# Stepper_motor_board.net
KiCad netlist of a schematic drawn in EAGLE
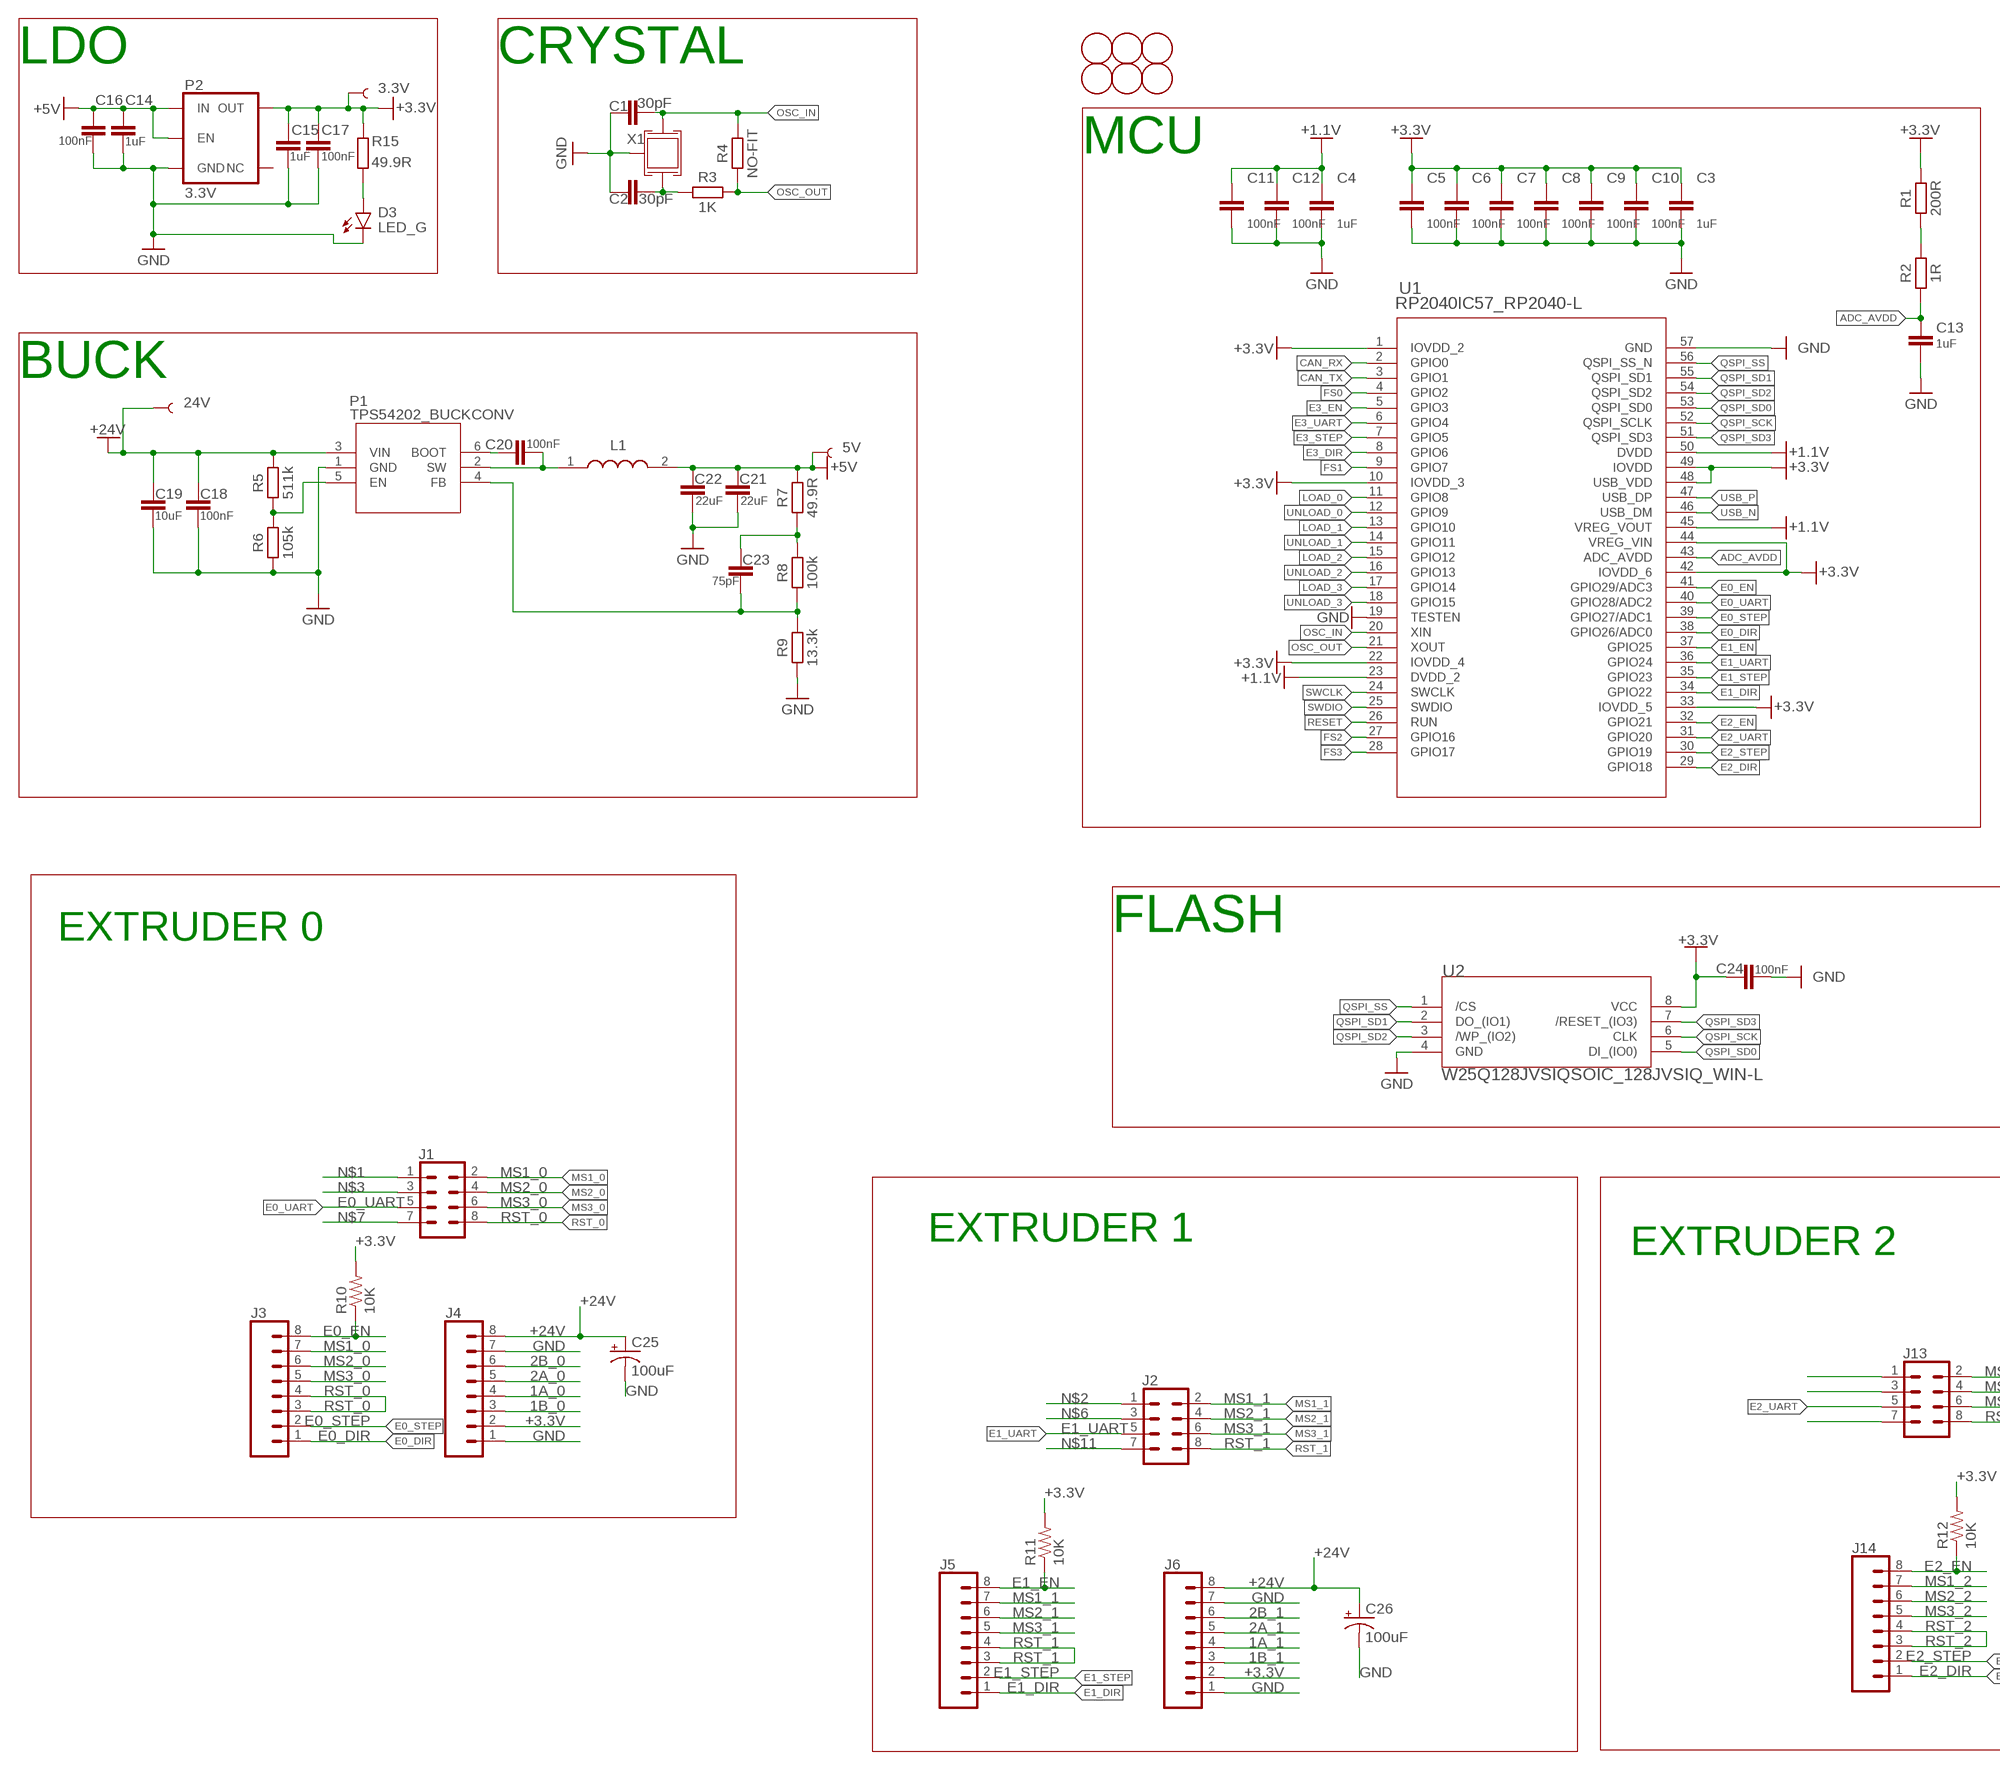
[diagram p0: schematic, sheet 1, part 1 of 2]
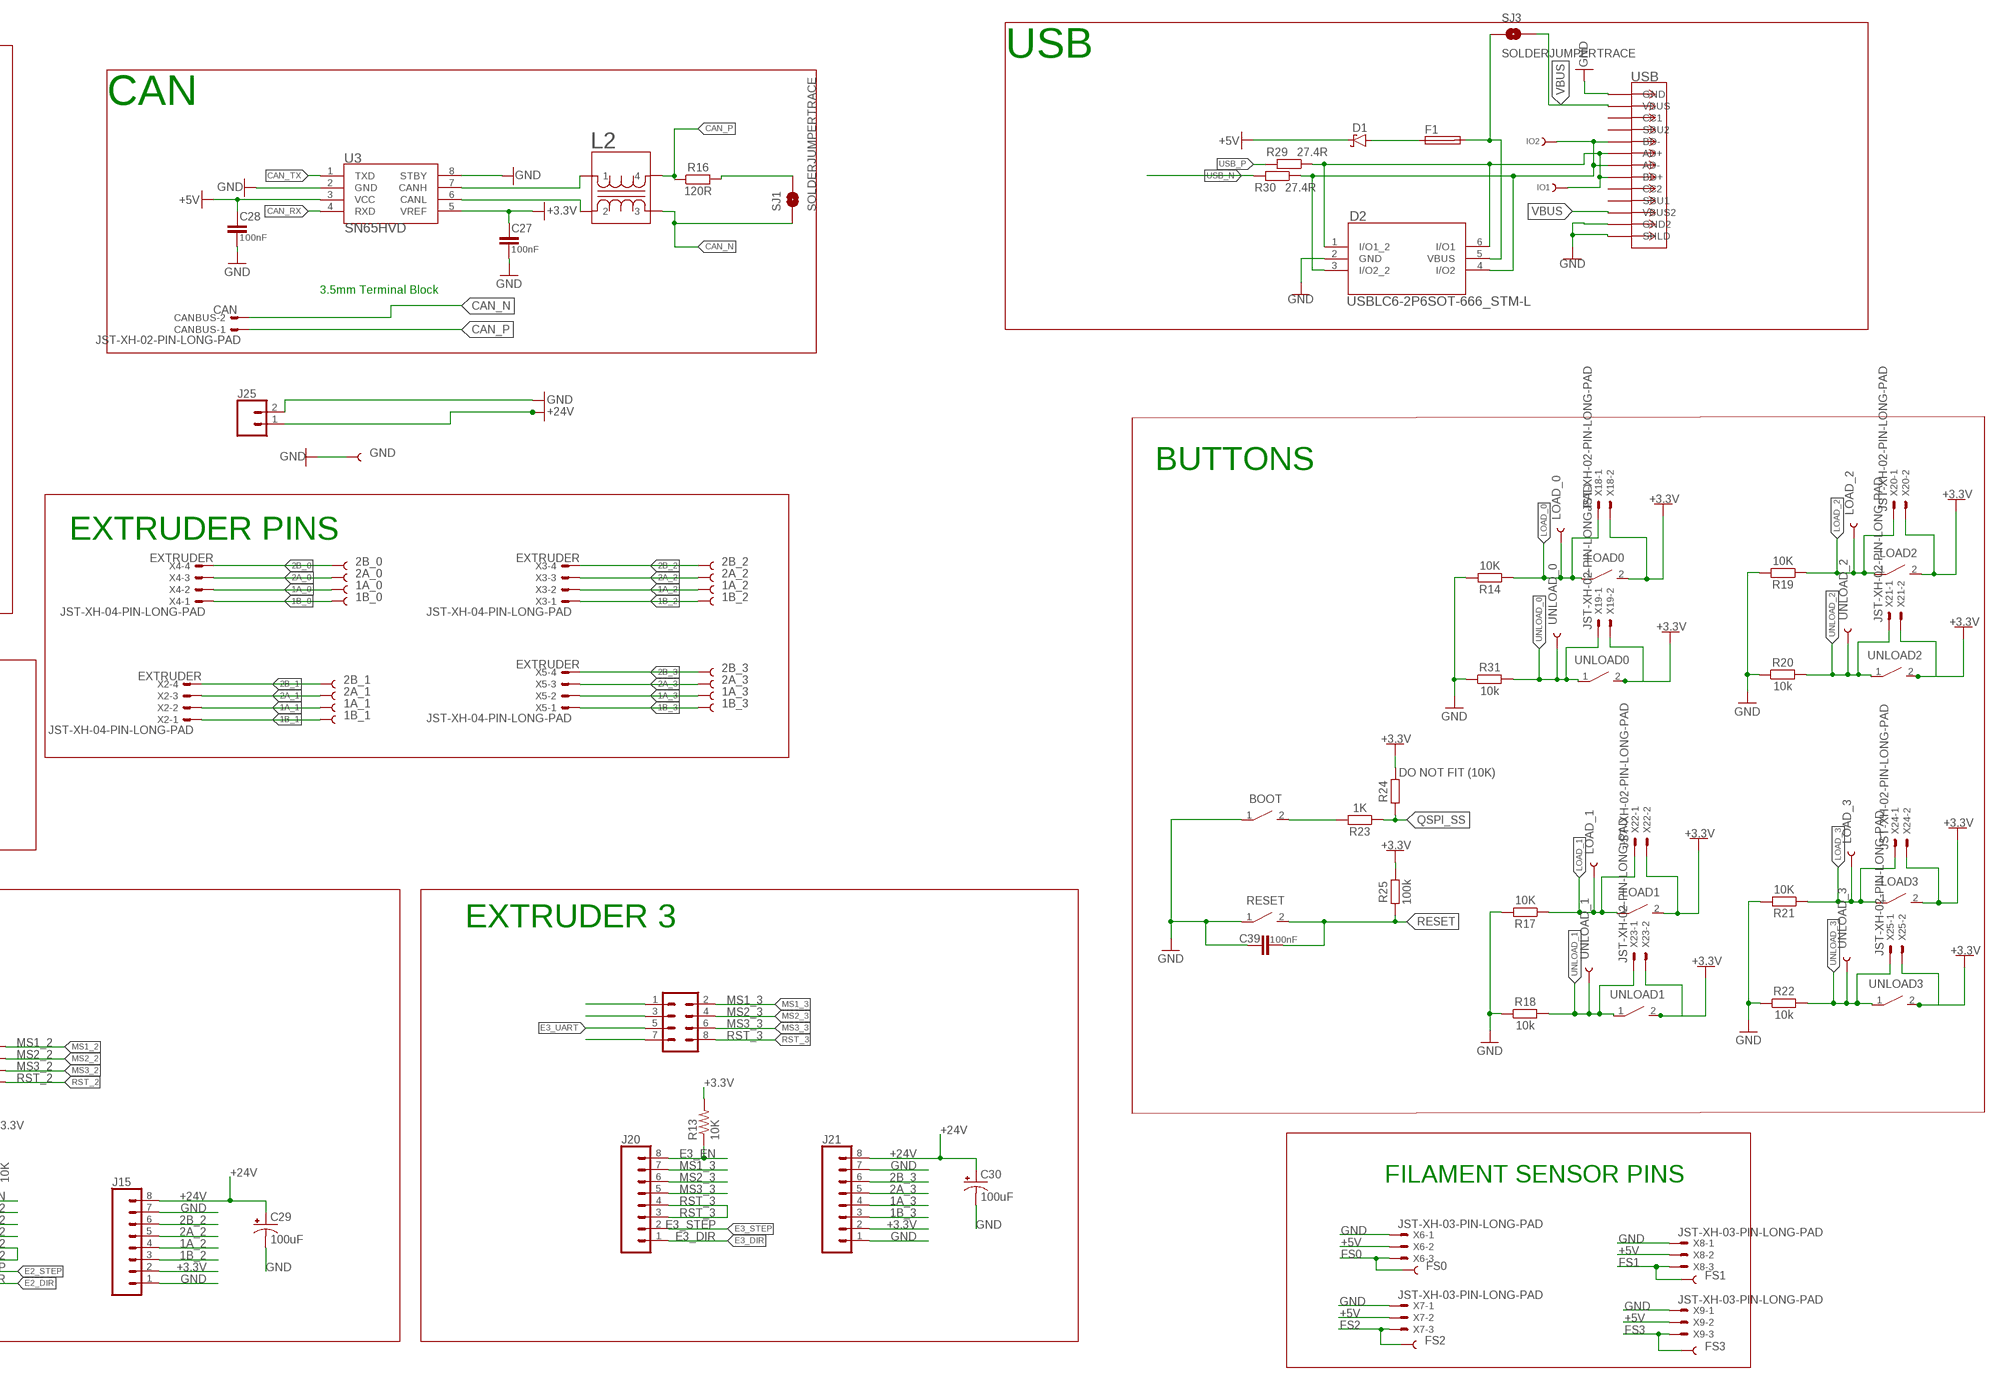
[diagram p1: schematic, sheet 1, part 2 of 2]

(export (version "E")
  (design (tool "Eeschema 10.0.6"))
  (components
    (comp (ref "1A_0")
      (value "TEST-POINT3X4")
      (footprint "eagle-import:PAD.03X.04")
      (libsource (lib "eagle-import") (part "TEST-POINT3X4"))
    )
    (comp (ref "1A_1")
      (value "TEST-POINT3X4")
      (footprint "eagle-import:PAD.03X.04")
      (libsource (lib "eagle-import") (part "TEST-POINT3X4"))
    )
    (comp (ref "1A_2")
      (value "TEST-POINT3X4")
      (footprint "eagle-import:PAD.03X.04")
      (libsource (lib "eagle-import") (part "TEST-POINT3X4"))
    )
    (comp (ref "1A_3")
      (value "TEST-POINT3X4")
      (footprint "eagle-import:PAD.03X.04")
      (libsource (lib "eagle-import") (part "TEST-POINT3X4"))
    )
    (comp (ref "1B_0")
      (value "TEST-POINT3X4")
      (footprint "eagle-import:PAD.03X.04")
      (libsource (lib "eagle-import") (part "TEST-POINT3X4"))
    )
    (comp (ref "1B_1")
      (value "TEST-POINT3X4")
      (footprint "eagle-import:PAD.03X.04")
      (libsource (lib "eagle-import") (part "TEST-POINT3X4"))
    )
    (comp (ref "1B_2")
      (value "TEST-POINT3X4")
      (footprint "eagle-import:PAD.03X.04")
      (libsource (lib "eagle-import") (part "TEST-POINT3X4"))
    )
    (comp (ref "1B_3")
      (value "TEST-POINT3X4")
      (footprint "eagle-import:PAD.03X.04")
      (libsource (lib "eagle-import") (part "TEST-POINT3X4"))
    )
    (comp (ref "2A_0")
      (value "TEST-POINT3X4")
      (footprint "eagle-import:PAD.03X.04")
      (libsource (lib "eagle-import") (part "TEST-POINT3X4"))
    )
    (comp (ref "2A_1")
      (value "TEST-POINT3X4")
      (footprint "eagle-import:PAD.03X.04")
      (libsource (lib "eagle-import") (part "TEST-POINT3X4"))
    )
    (comp (ref "2A_2")
      (value "TEST-POINT3X4")
      (footprint "eagle-import:PAD.03X.04")
      (libsource (lib "eagle-import") (part "TEST-POINT3X4"))
    )
    (comp (ref "2A_3")
      (value "TEST-POINT3X4")
      (footprint "eagle-import:PAD.03X.04")
      (libsource (lib "eagle-import") (part "TEST-POINT3X4"))
    )
    (comp (ref "2B_0")
      (value "TEST-POINT3X4")
      (footprint "eagle-import:PAD.03X.04")
      (libsource (lib "eagle-import") (part "TEST-POINT3X4"))
    )
    (comp (ref "2B_1")
      (value "TEST-POINT3X4")
      (footprint "eagle-import:PAD.03X.04")
      (libsource (lib "eagle-import") (part "TEST-POINT3X4"))
    )
    (comp (ref "2B_2")
      (value "TEST-POINT3X4")
      (footprint "eagle-import:PAD.03X.04")
      (libsource (lib "eagle-import") (part "TEST-POINT3X4"))
    )
    (comp (ref "2B_3")
      (value "TEST-POINT3X4")
      (footprint "eagle-import:PAD.03X.04")
      (libsource (lib "eagle-import") (part "TEST-POINT3X4"))
    )
    (comp (ref "3.3V")
      (value "TEST-POINT3X4")
      (footprint "eagle-import:PAD.03X.04")
      (libsource (lib "eagle-import") (part "TEST-POINT3X4"))
    )
    (comp (ref "5V")
      (value "TEST-POINT3X4")
      (footprint "eagle-import:PAD.03X.04")
      (libsource (lib "eagle-import") (part "TEST-POINT3X4"))
    )
    (comp (ref "24V")
      (value "TEST-POINT3X4")
      (footprint "eagle-import:PAD.03X.04")
      (libsource (lib "eagle-import") (part "TEST-POINT3X4"))
    )
    (comp (ref "BOOT")
      (value "B3U-1000P(M)-B")
      (footprint "eagle-import:B3U-1000P(M)-B")
      (fields (field (name "MANUFACTURER") "OMRON"))
      (libsource (lib "eagle-import") (part "B3U-X0001000P(M)-BB3U-1000P(M)-B"))
    )
    (comp (ref "C1")
      (value "30pF")
      (footprint "eagle-import:CAPC1005X60")
      (libsource (lib "eagle-import") (part "CCHIP-0402(1005-METRIC)_"))
    )
    (comp (ref "C2")
      (value "30pF")
      (footprint "eagle-import:CAPC1005X60")
      (libsource (lib "eagle-import") (part "CCHIP-0402(1005-METRIC)_"))
    )
    (comp (ref "C3")
      (value "1uF")
      (footprint "eagle-import:CAPC1005X60")
      (libsource (lib "eagle-import") (part "CCHIP-0402(1005-METRIC)_"))
    )
    (comp (ref "C4")
      (value "1uF")
      (footprint "eagle-import:CAPC1005X60")
      (libsource (lib "eagle-import") (part "CCHIP-0402(1005-METRIC)_"))
    )
    (comp (ref "C5")
      (value "100nF")
      (footprint "eagle-import:CAPC1005X60")
      (libsource (lib "eagle-import") (part "CCHIP-0402(1005-METRIC)_"))
    )
    (comp (ref "C6")
      (value "100nF")
      (footprint "eagle-import:CAPC1005X60")
      (libsource (lib "eagle-import") (part "CCHIP-0402(1005-METRIC)_"))
    )
    (comp (ref "C7")
      (value "100nF")
      (footprint "eagle-import:CAPC1005X60")
      (libsource (lib "eagle-import") (part "CCHIP-0402(1005-METRIC)_"))
    )
    (comp (ref "C8")
      (value "100nF")
      (footprint "eagle-import:CAPC1005X60")
      (libsource (lib "eagle-import") (part "CCHIP-0402(1005-METRIC)_"))
    )
    (comp (ref "C9")
      (value "100nF")
      (footprint "eagle-import:CAPC1005X60")
      (libsource (lib "eagle-import") (part "CCHIP-0402(1005-METRIC)_"))
    )
    (comp (ref "C10")
      (value "100nF")
      (footprint "eagle-import:CAPC1005X60")
      (libsource (lib "eagle-import") (part "CCHIP-0402(1005-METRIC)_"))
    )
    (comp (ref "C11")
      (value "100nF")
      (footprint "eagle-import:CAPC1005X60")
      (libsource (lib "eagle-import") (part "CCHIP-0402(1005-METRIC)_"))
    )
    (comp (ref "C12")
      (value "100nF")
      (footprint "eagle-import:CAPC1005X60")
      (libsource (lib "eagle-import") (part "CCHIP-0402(1005-METRIC)_"))
    )
    (comp (ref "C13")
      (value "1uF")
      (footprint "eagle-import:CAPC1005X60")
      (libsource (lib "eagle-import") (part "CCHIP-0402(1005-METRIC)_"))
    )
    (comp (ref "C14")
      (value "1uF")
      (footprint "eagle-import:CAPC1005X60")
      (libsource (lib "eagle-import") (part "CCHIP-0402(1005-METRIC)_"))
    )
    (comp (ref "C15")
      (value "1uF")
      (footprint "eagle-import:CAPC1005X60")
      (libsource (lib "eagle-import") (part "CCHIP-0402(1005-METRIC)_"))
    )
    (comp (ref "C16")
      (value "100nF")
      (footprint "eagle-import:CAPC1005X60")
      (libsource (lib "eagle-import") (part "CCHIP-0402(1005-METRIC)_"))
    )
    (comp (ref "C17")
      (value "100nF")
      (footprint "eagle-import:CAPC1005X60")
      (libsource (lib "eagle-import") (part "CCHIP-0402(1005-METRIC)_"))
    )
    (comp (ref "C18")
      (value "100nF")
      (footprint "eagle-import:CAPC1005X60")
      (libsource (lib "eagle-import") (part "CCHIP-0402(1005-METRIC)_"))
    )
    (comp (ref "C19")
      (value "10uF")
      (footprint "eagle-import:CAPC1608X85")
      (libsource (lib "eagle-import") (part "CCHIP-0603(1608-METRIC)_"))
    )
    (comp (ref "C20")
      (value "100nF")
      (footprint "eagle-import:CAPC1005X60")
      (libsource (lib "eagle-import") (part "CCHIP-0402(1005-METRIC)_"))
    )
    (comp (ref "C21")
      (value "22uF")
      (footprint "eagle-import:CAPC2012X110")
      (libsource (lib "eagle-import") (part "CCHIP-0805(2012-METRIC)_"))
    )
    (comp (ref "C22")
      (value "22uF")
      (footprint "eagle-import:CAPC2012X110")
      (libsource (lib "eagle-import") (part "CCHIP-0805(2012-METRIC)_"))
    )
    (comp (ref "C23")
      (value "75pF")
      (footprint "eagle-import:CAPC1005X60")
      (libsource (lib "eagle-import") (part "CCHIP-0402(1005-METRIC)_"))
    )
    (comp (ref "C24")
      (value "100nF")
      (footprint "eagle-import:CAPC1005X60")
      (libsource (lib "eagle-import") (part "CCHIP-0402(1005-METRIC)_"))
    )
    (comp (ref "C25")
      (value "100uF")
      (footprint "eagle-import:PANASONIC_D")
      (libsource (lib "eagle-import") (part "100UF-POLAR-25V-20%(ELEC)"))
    )
    (comp (ref "C26")
      (value "100uF")
      (footprint "eagle-import:PANASONIC_D")
      (libsource (lib "eagle-import") (part "100UF-POLAR-25V-20%(ELEC)"))
    )
    (comp (ref "C27")
      (value "100nF")
      (footprint "eagle-import:CAPC1005X60")
      (libsource (lib "eagle-import") (part "CCHIP-0402(1005-METRIC)_"))
    )
    (comp (ref "C28")
      (value "100nF")
      (footprint "eagle-import:CAPC1005X60")
      (libsource (lib "eagle-import") (part "CCHIP-0402(1005-METRIC)_"))
    )
    (comp (ref "C29")
      (value "100uF")
      (footprint "eagle-import:PANASONIC_D")
      (libsource (lib "eagle-import") (part "100UF-POLAR-25V-20%(ELEC)"))
    )
    (comp (ref "C30")
      (value "100uF")
      (footprint "eagle-import:PANASONIC_D")
      (libsource (lib "eagle-import") (part "100UF-POLAR-25V-20%(ELEC)"))
    )
    (comp (ref "C39")
      (value "100nF")
      (footprint "eagle-import:CAPC1005X60")
      (libsource (lib "eagle-import") (part "CCHIP-0402(1005-METRIC)_"))
    )
    (comp (ref "CANBUS")
      (value "JST-XH-02-PIN-LONG-PAD")
      (footprint "eagle-import:JST-XH-02-PACKAGE-LONG-PAD")
      (libsource (lib "eagle-import") (part "JST-XH-02-PIN-LONG-PAD"))
    )
    (comp (ref "D1")
      (value "MBR0520LT1G")
      (footprint "eagle-import:SODFL3718X115")
      (fields (field (name "MANUFACTURER") "ON Semiconductor"))
      (libsource (lib "eagle-import") (part "SCHOTTKY_DO-219MBR0520LT1G"))
    )
    (comp (ref "D2")
      (value "USBLC6-2P6SOT-666_STM-L")
      (footprint "eagle-import:SOT-666_STM-L")
      (fields
        (field (name "MANUFACTURER_PART_NUMBER") "USBLC6-2P6")
        (field (name "COPYRIGHT") "Copyright (C) 2023 Ultra Librarian. All rights reserved.")
      )
      (libsource (lib "eagle-import") (part "USBLC6-2P6SOT-666_STM-L"))
    )
    (comp (ref "D3")
      (value "LED_G")
      (footprint "eagle-import:LEDC1608X35N_FLAT-G")
      (libsource (lib "eagle-import") (part "CHIP-FLAT-G_0603-0.35MM"))
    )
    (comp (ref "F1")
      (value "FUSE_CHIP-0603(1608-METRIC)")
      (footprint "eagle-import:FUSC1608X60N")
      (libsource (lib "eagle-import") (part "FUSECHIP-0603(1608-METRIC)_"))
    )
    (comp (ref "FD1")
      (value "FIDUCIAL")
      (footprint "eagle-import:FIDUCIAL_1MM")
      (libsource (lib "eagle-import") (part "FIDUCIAL"))
    )
    (comp (ref "FD2")
      (value "FIDUCIAL")
      (footprint "eagle-import:FIDUCIAL_1MM")
      (libsource (lib "eagle-import") (part "FIDUCIAL"))
    )
    (comp (ref "FD3")
      (value "FIDUCIAL")
      (footprint "eagle-import:FIDUCIAL_1MM")
      (libsource (lib "eagle-import") (part "FIDUCIAL"))
    )
    (comp (ref "FD4")
      (value "FIDUCIAL")
      (footprint "eagle-import:FIDUCIAL_1MM")
      (libsource (lib "eagle-import") (part "FIDUCIAL"))
    )
    (comp (ref "FD5")
      (value "FIDUCIAL")
      (footprint "eagle-import:FIDUCIAL_1MM")
      (libsource (lib "eagle-import") (part "FIDUCIAL"))
    )
    (comp (ref "FD6")
      (value "FIDUCIAL")
      (footprint "eagle-import:FIDUCIAL_1MM")
      (libsource (lib "eagle-import") (part "FIDUCIAL"))
    )
    (comp (ref "FS0")
      (value "TEST-POINT3X4")
      (footprint "eagle-import:PAD.03X.04")
      (libsource (lib "eagle-import") (part "TEST-POINT3X4"))
    )
    (comp (ref "FS1")
      (value "TEST-POINT3X4")
      (footprint "eagle-import:PAD.03X.04")
      (libsource (lib "eagle-import") (part "TEST-POINT3X4"))
    )
    (comp (ref "FS2")
      (value "TEST-POINT3X4")
      (footprint "eagle-import:PAD.03X.04")
      (libsource (lib "eagle-import") (part "TEST-POINT3X4"))
    )
    (comp (ref "FS3")
      (value "TEST-POINT3X4")
      (footprint "eagle-import:PAD.03X.04")
      (libsource (lib "eagle-import") (part "TEST-POINT3X4"))
    )
    (comp (ref "GND")
      (value "TEST-POINT3X4")
      (footprint "eagle-import:PAD.03X.04")
      (libsource (lib "eagle-import") (part "TEST-POINT3X4"))
    )
    (comp (ref "IO1")
      (value "TEST-POINT3")
      (footprint "eagle-import:PAD.03X.03")
      (libsource (lib "eagle-import") (part "TEST-POINT3"))
    )
    (comp (ref "IO2")
      (value "TEST-POINT3")
      (footprint "eagle-import:PAD.03X.03")
      (libsource (lib "eagle-import") (part "TEST-POINT3"))
    )
    (comp (ref "J1")
      (value "CONN_04X2")
      (footprint "eagle-import:2X4")
      (libsource (lib "eagle-import") (part "CONN_04X2"))
    )
    (comp (ref "J2")
      (value "CONN_04X2")
      (footprint "eagle-import:2X4")
      (libsource (lib "eagle-import") (part "CONN_04X2"))
    )
    (comp (ref "J3")
      (value "CONN_08\"")
      (footprint "eagle-import:1X08")
      (libsource (lib "eagle-import") (part "CONN_08{dblquote}"))
    )
    (comp (ref "J4")
      (value "CONN_08\"")
      (footprint "eagle-import:1X08")
      (libsource (lib "eagle-import") (part "CONN_08{dblquote}"))
    )
    (comp (ref "J5")
      (value "CONN_08\"")
      (footprint "eagle-import:1X08")
      (libsource (lib "eagle-import") (part "CONN_08{dblquote}"))
    )
    (comp (ref "J6")
      (value "CONN_08\"")
      (footprint "eagle-import:1X08")
      (libsource (lib "eagle-import") (part "CONN_08{dblquote}"))
    )
    (comp (ref "J13")
      (value "CONN_04X2")
      (footprint "eagle-import:2X4")
      (libsource (lib "eagle-import") (part "CONN_04X2"))
    )
    (comp (ref "J14")
      (value "CONN_08\"")
      (footprint "eagle-import:1X08")
      (libsource (lib "eagle-import") (part "CONN_08{dblquote}"))
    )
    (comp (ref "J15")
      (value "CONN_08\"")
      (footprint "eagle-import:1X08")
      (libsource (lib "eagle-import") (part "CONN_08{dblquote}"))
    )
    (comp (ref "J19")
      (value "CONN_04X2")
      (footprint "eagle-import:2X4")
      (libsource (lib "eagle-import") (part "CONN_04X2"))
    )
    (comp (ref "J20")
      (value "CONN_08\"")
      (footprint "eagle-import:1X08")
      (libsource (lib "eagle-import") (part "CONN_08{dblquote}"))
    )
    (comp (ref "J21")
      (value "CONN_08\"")
      (footprint "eagle-import:1X08")
      (libsource (lib "eagle-import") (part "CONN_08{dblquote}"))
    )
    (comp (ref "J25")
      (value "CONN_023.5MM")
      (footprint "eagle-import:SCREWTERMINAL-3.5MM-2")
      (libsource (lib "eagle-import") (part "CONN_023.5MM"))
    )
    (comp (ref "L1")
      (value "ASPI-0630HI-100M-T157X7X4")
      (footprint "eagle-import:SMDRI74-680MT")
      (libsource (lib "eagle-import") (part "ASPI-0630HI-100M-T157X7X4"))
    )
    (comp (ref "L2")
      (value "ACM2012")
      (footprint "eagle-import:ACM2012_TDK")
      (fields
        (field (name "MANUFACTURER_PART_NUMBER") "ACM2012-201-2P-T002")
        (field (name "COPYRIGHT") "Copyright (C) 2023 Ultra Librarian. All rights reserved.")
      )
      (libsource (lib "eagle-import") (part "ACM2012-201-2P-T002ACM2012_TDK"))
    )
    (comp (ref "LOAD0")
      (value "B3U-1000P(M)-B")
      (footprint "eagle-import:B3U-1000P(M)-B")
      (fields (field (name "MANUFACTURER") "OMRON"))
      (libsource (lib "eagle-import") (part "B3U-X0001000P(M)-BB3U-1000P(M)-B"))
    )
    (comp (ref "LOAD1")
      (value "B3U-1000P(M)-B")
      (footprint "eagle-import:B3U-1000P(M)-B")
      (fields (field (name "MANUFACTURER") "OMRON"))
      (libsource (lib "eagle-import") (part "B3U-X0001000P(M)-BB3U-1000P(M)-B"))
    )
    (comp (ref "LOAD2")
      (value "B3U-1000P(M)-B")
      (footprint "eagle-import:B3U-1000P(M)-B")
      (fields (field (name "MANUFACTURER") "OMRON"))
      (libsource (lib "eagle-import") (part "B3U-X0001000P(M)-BB3U-1000P(M)-B"))
    )
    (comp (ref "LOAD3")
      (value "B3U-1000P(M)-B")
      (footprint "eagle-import:B3U-1000P(M)-B")
      (fields (field (name "MANUFACTURER") "OMRON"))
      (libsource (lib "eagle-import") (part "B3U-X0001000P(M)-BB3U-1000P(M)-B"))
    )
    (comp (ref "LOAD_0")
      (value "TEST-POINT3X4")
      (footprint "eagle-import:PAD.03X.04")
      (libsource (lib "eagle-import") (part "TEST-POINT3X4"))
    )
    (comp (ref "LOAD_1")
      (value "TEST-POINT3X4")
      (footprint "eagle-import:PAD.03X.04")
      (libsource (lib "eagle-import") (part "TEST-POINT3X4"))
    )
    (comp (ref "LOAD_2")
      (value "TEST-POINT3X4")
      (footprint "eagle-import:PAD.03X.04")
      (libsource (lib "eagle-import") (part "TEST-POINT3X4"))
    )
    (comp (ref "LOAD_3")
      (value "TEST-POINT3X4")
      (footprint "eagle-import:PAD.03X.04")
      (libsource (lib "eagle-import") (part "TEST-POINT3X4"))
    )
    (comp (ref "P1")
      (value "TPS54202_BUCKCONV")
      (footprint "eagle-import:SOT-23-6")
      (libsource (lib "eagle-import") (part "TPS54202_BUCKCONV"))
    )
    (comp (ref "P2")
      (value "3.3V")
      (footprint "eagle-import:SOT23-5")
      (libsource (lib "eagle-import") (part "V_REG_AP2112K-3.3V"))
    )
    (comp (ref "R1")
      (value "200R")
      (footprint "eagle-import:RESC1005X40")
      (libsource (lib "eagle-import") (part "RCHIP-0402(1005-METRIC)_"))
    )
    (comp (ref "R2")
      (value "1R")
      (footprint "eagle-import:RESC1005X40")
      (libsource (lib "eagle-import") (part "RCHIP-0402(1005-METRIC)_"))
    )
    (comp (ref "R3")
      (value "1K")
      (footprint "eagle-import:RESC1005X40")
      (libsource (lib "eagle-import") (part "RCHIP-0402(1005-METRIC)_"))
    )
    (comp (ref "R4")
      (value "NO-FIT")
      (footprint "eagle-import:RESC1005X40")
      (libsource (lib "eagle-import") (part "RCHIP-0402(1005-METRIC)_"))
    )
    (comp (ref "R5")
      (value "511k")
      (footprint "eagle-import:RESC1005X40")
      (libsource (lib "eagle-import") (part "RCHIP-0402(1005-METRIC)_"))
    )
    (comp (ref "R6")
      (value "105k")
      (footprint "eagle-import:RESC1005X40")
      (libsource (lib "eagle-import") (part "RCHIP-0402(1005-METRIC)_"))
    )
    (comp (ref "R7")
      (value "49.9R")
      (footprint "eagle-import:RESC1005X40")
      (libsource (lib "eagle-import") (part "RCHIP-0402(1005-METRIC)_"))
    )
    (comp (ref "R8")
      (value "100k")
      (footprint "eagle-import:RESC1005X40")
      (libsource (lib "eagle-import") (part "RCHIP-0402(1005-METRIC)_"))
    )
    (comp (ref "R9")
      (value "13.3k")
      (footprint "eagle-import:RESC1005X40")
      (libsource (lib "eagle-import") (part "RCHIP-0402(1005-METRIC)_"))
    )
    (comp (ref "R10")
      (value "10K")
      (footprint "eagle-import:0603-RES")
      (libsource (lib "eagle-import") (part "10KOHM1/10W1%(0603)0603"))
    )
    (comp (ref "R11")
      (value "10K")
      (footprint "eagle-import:0603-RES")
      (libsource (lib "eagle-import") (part "10KOHM1/10W1%(0603)0603"))
    )
    (comp (ref "R12")
      (value "10K")
      (footprint "eagle-import:0603-RES")
      (libsource (lib "eagle-import") (part "10KOHM1/10W1%(0603)0603"))
    )
    (comp (ref "R13")
      (value "10K")
      (footprint "eagle-import:0603-RES")
      (libsource (lib "eagle-import") (part "10KOHM1/10W1%(0603)0603"))
    )
    (comp (ref "R14")
      (value "10K")
      (footprint "eagle-import:RESC1005X40")
      (libsource (lib "eagle-import") (part "RCHIP-0402(1005-METRIC)_"))
    )
    (comp (ref "R15")
      (value "49.9R")
      (footprint "eagle-import:RESC1005X40")
      (libsource (lib "eagle-import") (part "RCHIP-0402(1005-METRIC)_"))
    )
    (comp (ref "R16")
      (value "120R")
      (footprint "eagle-import:RESC1005X40")
      (libsource (lib "eagle-import") (part "RCHIP-0402(1005-METRIC)_"))
    )
    (comp (ref "R17")
      (value "10K")
      (footprint "eagle-import:RESC1005X40")
      (libsource (lib "eagle-import") (part "RCHIP-0402(1005-METRIC)_"))
    )
    (comp (ref "R18")
      (value "10k")
      (footprint "eagle-import:RESC1005X40")
      (libsource (lib "eagle-import") (part "Fracktal_Misc_Lib_v26_RCHIP-0402(1005-METRIC)_"))
    )
    (comp (ref "R19")
      (value "10K")
      (footprint "eagle-import:RESC1005X40")
      (libsource (lib "eagle-import") (part "RCHIP-0402(1005-METRIC)_"))
    )
    (comp (ref "R20")
      (value "10k")
      (footprint "eagle-import:RESC1005X40")
      (libsource (lib "eagle-import") (part "Fracktal_Misc_Lib_v26_RCHIP-0402(1005-METRIC)_"))
    )
    (comp (ref "R21")
      (value "10K")
      (footprint "eagle-import:RESC1005X40")
      (libsource (lib "eagle-import") (part "RCHIP-0402(1005-METRIC)_"))
    )
    (comp (ref "R22")
      (value "10k")
      (footprint "eagle-import:RESC1005X40")
      (libsource (lib "eagle-import") (part "Fracktal_Misc_Lib_v26_RCHIP-0402(1005-METRIC)_"))
    )
    (comp (ref "R23")
      (value "1K")
      (footprint "eagle-import:RESC1005X40")
      (libsource (lib "eagle-import") (part "RCHIP-0402(1005-METRIC)_"))
    )
    (comp (ref "R24")
      (value "DO NOT FIT (10K)")
      (footprint "eagle-import:RESC1005X40")
      (libsource (lib "eagle-import") (part "RCHIP-0402(1005-METRIC)_"))
    )
    (comp (ref "R25")
      (value "100k")
      (footprint "eagle-import:RESC1005X40")
      (libsource (lib "eagle-import") (part "RCHIP-0402(1005-METRIC)_"))
    )
    (comp (ref "R29")
      (value "27.4R")
      (footprint "eagle-import:RESC1005X40")
      (libsource (lib "eagle-import") (part "RCHIP-0402(1005-METRIC)_"))
    )
    (comp (ref "R30")
      (value "27.4R")
      (footprint "eagle-import:RESC1005X40")
      (libsource (lib "eagle-import") (part "RCHIP-0402(1005-METRIC)_"))
    )
    (comp (ref "R31")
      (value "10k")
      (footprint "eagle-import:RESC1005X40")
      (libsource (lib "eagle-import") (part "Fracktal_Misc_Lib_v26_RCHIP-0402(1005-METRIC)_"))
    )
    (comp (ref "RESET")
      (value "B3U-1000P(M)-B")
      (footprint "eagle-import:B3U-1000P(M)-B")
      (fields (field (name "MANUFACTURER") "OMRON"))
      (libsource (lib "eagle-import") (part "B3U-X0001000P(M)-BB3U-1000P(M)-B"))
    )
    (comp (ref "SJ1")
      (value "SOLDERJUMPERTRACE")
      (footprint "eagle-import:SJ_2S-TRACE")
      (libsource (lib "eagle-import") (part "SOLDERJUMPERTRACE"))
    )
    (comp (ref "SJ3")
      (value "SOLDERJUMPERTRACE")
      (footprint "eagle-import:SJ_2S-TRACE")
      (libsource (lib "eagle-import") (part "SOLDERJUMPERTRACE"))
    )
    (comp (ref "U1")
      (value "RP2040IC57_RP2040-L")
      (footprint "eagle-import:IC57_RP2040-L")
      (fields
        (field (name "MANUFACTURER_PART_NUMBER") "RP2040")
        (field (name "COPYRIGHT") "Copyright (C) 2023 Ultra Librarian. All rights reserved.")
      )
      (libsource (lib "eagle-import") (part "RP2040IC57_RP2040-L"))
    )
    (comp (ref "U2")
      (value "W25Q128JVSIQSOIC_128JVSIQ_WIN-L")
      (footprint "eagle-import:SOIC_128JVSIQ_WIN-L")
      (fields
        (field (name "MANUFACTURER_PART_NUMBER") "W25Q128JVSIQ")
        (field (name "COPYRIGHT") "Copyright (C) 2023 Ultra Librarian. All rights reserved.")
      )
      (libsource (lib "eagle-import") (part "W25Q128JVSIQSOIC_128JVSIQ_WIN-L"))
    )
    (comp (ref "U3")
      (value "SN65HVD")
      (footprint "eagle-import:D8-L")
      (fields
        (field (name "MANUFACTURER_PART_NUMBER") "SN65HVD1050DR")
        (field (name "COPYRIGHT") "Copyright (C) 2023 Ultra Librarian. All rights reserved.")
      )
      (libsource (lib "eagle-import") (part "SN65HVD1050DRD8-L"))
    )
    (comp (ref "UNLOAD0")
      (value "B3U-1000P(M)-B")
      (footprint "eagle-import:B3U-1000P(M)-B")
      (fields (field (name "MANUFACTURER") "OMRON"))
      (libsource (lib "eagle-import") (part "B3U-X0001000P(M)-BB3U-1000P(M)-B"))
    )
    (comp (ref "UNLOAD1")
      (value "B3U-1000P(M)-B")
      (footprint "eagle-import:B3U-1000P(M)-B")
      (fields (field (name "MANUFACTURER") "OMRON"))
      (libsource (lib "eagle-import") (part "B3U-X0001000P(M)-BB3U-1000P(M)-B"))
    )
    (comp (ref "UNLOAD2")
      (value "B3U-1000P(M)-B")
      (footprint "eagle-import:B3U-1000P(M)-B")
      (fields (field (name "MANUFACTURER") "OMRON"))
      (libsource (lib "eagle-import") (part "B3U-X0001000P(M)-BB3U-1000P(M)-B"))
    )
    (comp (ref "UNLOAD3")
      (value "B3U-1000P(M)-B")
      (footprint "eagle-import:B3U-1000P(M)-B")
      (fields (field (name "MANUFACTURER") "OMRON"))
      (libsource (lib "eagle-import") (part "B3U-X0001000P(M)-BB3U-1000P(M)-B"))
    )
    (comp (ref "UNLOAD_0")
      (value "TEST-POINT3X4")
      (footprint "eagle-import:PAD.03X.04")
      (libsource (lib "eagle-import") (part "TEST-POINT3X4"))
    )
    (comp (ref "UNLOAD_1")
      (value "TEST-POINT3X4")
      (footprint "eagle-import:PAD.03X.04")
      (libsource (lib "eagle-import") (part "TEST-POINT3X4"))
    )
    (comp (ref "UNLOAD_2")
      (value "TEST-POINT3X4")
      (footprint "eagle-import:PAD.03X.04")
      (libsource (lib "eagle-import") (part "TEST-POINT3X4"))
    )
    (comp (ref "UNLOAD_3")
      (value "TEST-POINT3X4")
      (footprint "eagle-import:PAD.03X.04")
      (libsource (lib "eagle-import") (part "TEST-POINT3X4"))
    )
    (comp (ref "USB")
      (value "USB-C(KH-TYPE-C-16P)")
      (footprint "eagle-import:CONN12_KH-TYPE-C-16P")
      (fields
        (field (name "MANUFACTURER_PART_NUMBER") "DX07S016JA1R1500")
        (field (name "VENDOR") "LCSC")
        (field (name "COPYRIGHT") "Copyright (C) 2018 Accelerated Designs. All rights reserved")
        (field (name "SOURCELIBRARY") "JAE_Electronics_2020-03-30")
      )
      (libsource (lib "eagle-import") (part "USB-C(KH-TYPE-C-16P)"))
    )
    (comp (ref "X1")
      (value "CRYSTAL_TAXM12M4RLBDDT2T_3225")
      (footprint "eagle-import:CRYSTAL_3225")
      (libsource (lib "eagle-import") (part "CRYSTAL_TAXM12M4RLBDDT2T_3225"))
    )
    (comp (ref "X2")
      (value "JST-XH-04-PIN-LONG-PAD")
      (footprint "eagle-import:JST-XH-04-PACKAGE-LONG-PAD")
      (libsource (lib "eagle-import") (part "JST-XH-04-PIN-LONG-PAD"))
    )
    (comp (ref "X3")
      (value "JST-XH-04-PIN-LONG-PAD")
      (footprint "eagle-import:JST-XH-04-PACKAGE-LONG-PAD")
      (libsource (lib "eagle-import") (part "JST-XH-04-PIN-LONG-PAD"))
    )
    (comp (ref "X4")
      (value "JST-XH-04-PIN-LONG-PAD")
      (footprint "eagle-import:JST-XH-04-PACKAGE-LONG-PAD")
      (libsource (lib "eagle-import") (part "JST-XH-04-PIN-LONG-PAD"))
    )
    (comp (ref "X5")
      (value "JST-XH-04-PIN-LONG-PAD")
      (footprint "eagle-import:JST-XH-04-PACKAGE-LONG-PAD")
      (libsource (lib "eagle-import") (part "JST-XH-04-PIN-LONG-PAD"))
    )
    (comp (ref "X6")
      (value "JST-XH-03-PIN-LONG-PAD")
      (footprint "eagle-import:JST-XH-03-PACKAGE-LONG-PAD")
      (libsource (lib "eagle-import") (part "JST-XH-03-PIN-LONG-PAD"))
    )
    (comp (ref "X7")
      (value "JST-XH-03-PIN-LONG-PAD")
      (footprint "eagle-import:JST-XH-03-PACKAGE-LONG-PAD")
      (libsource (lib "eagle-import") (part "JST-XH-03-PIN-LONG-PAD"))
    )
    (comp (ref "X8")
      (value "JST-XH-03-PIN-LONG-PAD")
      (footprint "eagle-import:JST-XH-03-PACKAGE-LONG-PAD")
      (libsource (lib "eagle-import") (part "JST-XH-03-PIN-LONG-PAD"))
    )
    (comp (ref "X9")
      (value "JST-XH-03-PIN-LONG-PAD")
      (footprint "eagle-import:JST-XH-03-PACKAGE-LONG-PAD")
      (libsource (lib "eagle-import") (part "JST-XH-03-PIN-LONG-PAD"))
    )
    (comp (ref "X18")
      (value "JST-XH-02-PIN-LONG-PAD")
      (footprint "eagle-import:JST-XH-02-PACKAGE-LONG-PAD")
      (libsource (lib "eagle-import") (part "JST-XH-02-PIN-LONG-PAD"))
    )
    (comp (ref "X19")
      (value "JST-XH-02-PIN-LONG-PAD")
      (footprint "eagle-import:JST-XH-02-PACKAGE-LONG-PAD")
      (libsource (lib "eagle-import") (part "JST-XH-02-PIN-LONG-PAD"))
    )
    (comp (ref "X20")
      (value "JST-XH-02-PIN-LONG-PAD")
      (footprint "eagle-import:JST-XH-02-PACKAGE-LONG-PAD")
      (libsource (lib "eagle-import") (part "JST-XH-02-PIN-LONG-PAD"))
    )
    (comp (ref "X21")
      (value "JST-XH-02-PIN-LONG-PAD")
      (footprint "eagle-import:JST-XH-02-PACKAGE-LONG-PAD")
      (libsource (lib "eagle-import") (part "JST-XH-02-PIN-LONG-PAD"))
    )
    (comp (ref "X22")
      (value "JST-XH-02-PIN-LONG-PAD")
      (footprint "eagle-import:JST-XH-02-PACKAGE-LONG-PAD")
      (libsource (lib "eagle-import") (part "JST-XH-02-PIN-LONG-PAD"))
    )
    (comp (ref "X23")
      (value "JST-XH-02-PIN-LONG-PAD")
      (footprint "eagle-import:JST-XH-02-PACKAGE-LONG-PAD")
      (libsource (lib "eagle-import") (part "JST-XH-02-PIN-LONG-PAD"))
    )
    (comp (ref "X24")
      (value "JST-XH-02-PIN-LONG-PAD")
      (footprint "eagle-import:JST-XH-02-PACKAGE-LONG-PAD")
      (libsource (lib "eagle-import") (part "JST-XH-02-PIN-LONG-PAD"))
    )
    (comp (ref "X25")
      (value "JST-XH-02-PIN-LONG-PAD")
      (footprint "eagle-import:JST-XH-02-PACKAGE-LONG-PAD")
      (libsource (lib "eagle-import") (part "JST-XH-02-PIN-LONG-PAD"))
    )
  )
  (nets
    (net (code "1") (name "+1.1V") (class "Default")
      (node (ref "C11") (pin "1") (pinfunction "1_1") (pintype "passive"))
      (node (ref "C12") (pin "1") (pinfunction "1_1") (pintype "passive"))
      (node (ref "C4") (pin "1") (pinfunction "1_1") (pintype "passive"))
      (node (ref "U1") (pin "23") (pinfunction "DVDD_2_23") (pintype "power_in"))
      (node (ref "U1") (pin "45") (pinfunction "VREG_VOUT_45") (pintype "output"))
      (node (ref "U1") (pin "50") (pinfunction "DVDD_50") (pintype "power_in"))
    )
    (net (code "2") (name "+3.3V") (class "Default")
      (node (ref "3.3V") (pin "P$1") (pinfunction "1_P$1") (pintype "bidirectional"))
      (node (ref "C10") (pin "1") (pinfunction "1_1") (pintype "passive"))
      (node (ref "C15") (pin "1") (pinfunction "1_1") (pintype "passive"))
      (node (ref "C17") (pin "1") (pinfunction "1_1") (pintype "passive"))
      (node (ref "C24") (pin "1") (pinfunction "1_1") (pintype "passive"))
      (node (ref "C27") (pin "1") (pinfunction "1_1") (pintype "passive"))
      (node (ref "C3") (pin "1") (pinfunction "1_1") (pintype "passive"))
      (node (ref "C5") (pin "1") (pinfunction "1_1") (pintype "passive"))
      (node (ref "C6") (pin "1") (pinfunction "1_1") (pintype "passive"))
      (node (ref "C7") (pin "1") (pinfunction "1_1") (pintype "passive"))
      (node (ref "C8") (pin "1") (pinfunction "1_1") (pintype "passive"))
      (node (ref "C9") (pin "1") (pinfunction "1_1") (pintype "passive"))
      (node (ref "J15") (pin "2") (pinfunction "2_2") (pintype "passive"))
      (node (ref "J21") (pin "2") (pinfunction "2_2") (pintype "passive"))
      (node (ref "J4") (pin "2") (pinfunction "2_2") (pintype "passive"))
      (node (ref "J6") (pin "2") (pinfunction "2_2") (pintype "passive"))
      (node (ref "LOAD0") (pin "2") (pinfunction "2_2") (pintype "bidirectional"))
      (node (ref "LOAD1") (pin "2") (pinfunction "2_2") (pintype "bidirectional"))
      (node (ref "LOAD2") (pin "2") (pinfunction "2_2") (pintype "bidirectional"))
      (node (ref "LOAD3") (pin "2") (pinfunction "2_2") (pintype "bidirectional"))
      (node (ref "P2") (pin "5") (pinfunction "OUT_5") (pintype "passive"))
      (node (ref "R1") (pin "2") (pinfunction "2_2") (pintype "passive"))
      (node (ref "R10") (pin "2") (pinfunction "2_2") (pintype "passive"))
      (node (ref "R11") (pin "2") (pinfunction "2_2") (pintype "passive"))
      (node (ref "R12") (pin "2") (pinfunction "2_2") (pintype "passive"))
      (node (ref "R13") (pin "2") (pinfunction "2_2") (pintype "passive"))
      (node (ref "R15") (pin "2") (pinfunction "2_2") (pintype "passive"))
      (node (ref "R24") (pin "2") (pinfunction "2_2") (pintype "passive"))
      (node (ref "R25") (pin "2") (pinfunction "2_2") (pintype "passive"))
      (node (ref "U1") (pin "1") (pinfunction "IOVDD_2_1") (pintype "power_in"))
      (node (ref "U1") (pin "10") (pinfunction "IOVDD_3_10") (pintype "power_in"))
      (node (ref "U1") (pin "22") (pinfunction "IOVDD_4_22") (pintype "power_in"))
      (node (ref "U1") (pin "33") (pinfunction "IOVDD_5_33") (pintype "power_in"))
      (node (ref "U1") (pin "42") (pinfunction "IOVDD_6_42") (pintype "power_in"))
      (node (ref "U1") (pin "44") (pinfunction "VREG_VIN_44") (pintype "passive"))
      (node (ref "U1") (pin "48") (pinfunction "USB_VDD_48") (pintype "power_in"))
      (node (ref "U1") (pin "49") (pinfunction "IOVDD_49") (pintype "power_in"))
      (node (ref "U2") (pin "8") (pinfunction "VCC_8") (pintype "power_in"))
      (node (ref "U3") (pin "5") (pinfunction "VREF_5") (pintype "power_in"))
      (node (ref "UNLOAD0") (pin "2") (pinfunction "2_2") (pintype "bidirectional"))
      (node (ref "UNLOAD1") (pin "2") (pinfunction "2_2") (pintype "bidirectional"))
      (node (ref "UNLOAD2") (pin "2") (pinfunction "2_2") (pintype "bidirectional"))
      (node (ref "UNLOAD3") (pin "2") (pinfunction "2_2") (pintype "bidirectional"))
      (node (ref "X18") (pin "2") (pinfunction "S_2") (pintype "passive"))
      (node (ref "X19") (pin "2") (pinfunction "S_2") (pintype "passive"))
      (node (ref "X20") (pin "2") (pinfunction "S_2") (pintype "passive"))
      (node (ref "X21") (pin "2") (pinfunction "S_2") (pintype "passive"))
      (node (ref "X22") (pin "2") (pinfunction "S_2") (pintype "passive"))
      (node (ref "X23") (pin "2") (pinfunction "S_2") (pintype "passive"))
      (node (ref "X24") (pin "2") (pinfunction "S_2") (pintype "passive"))
      (node (ref "X25") (pin "2") (pinfunction "S_2") (pintype "passive"))
    )
    (net (code "3") (name "+5V") (class "Default")
      (node (ref "5V") (pin "P$1") (pinfunction "1_P$1") (pintype "bidirectional"))
      (node (ref "C14") (pin "1") (pinfunction "1_1") (pintype "passive"))
      (node (ref "C16") (pin "1") (pinfunction "1_1") (pintype "passive"))
      (node (ref "C21") (pin "1") (pinfunction "1_1") (pintype "passive"))
      (node (ref "C22") (pin "1") (pinfunction "1_1") (pintype "passive"))
      (node (ref "C28") (pin "1") (pinfunction "1_1") (pintype "passive"))
      (node (ref "D1") (pin "1") (pinfunction "C_1") (pintype "passive"))
      (node (ref "L1") (pin "2") (pinfunction "2_2") (pintype "bidirectional"))
      (node (ref "P2") (pin "1") (pinfunction "IN_1") (pintype "input"))
      (node (ref "P2") (pin "3") (pinfunction "EN_3") (pintype "input"))
      (node (ref "R7") (pin "2") (pinfunction "2_2") (pintype "passive"))
      (node (ref "U3") (pin "3") (pinfunction "VCC_3") (pintype "power_in"))
      (node (ref "X6") (pin "2") (pinfunction "S_2") (pintype "passive"))
      (node (ref "X7") (pin "2") (pinfunction "S_2") (pintype "passive"))
      (node (ref "X8") (pin "2") (pinfunction "S_2") (pintype "passive"))
      (node (ref "X9") (pin "2") (pinfunction "S_2") (pintype "passive"))
    )
    (net (code "4") (name "+24V") (class "Default")
      (node (ref "24V") (pin "P$1") (pinfunction "1_P$1") (pintype "bidirectional"))
      (node (ref "C18") (pin "1") (pinfunction "1_1") (pintype "passive"))
      (node (ref "C19") (pin "1") (pinfunction "1_1") (pintype "passive"))
      (node (ref "C25") (pin "+") (pinfunction "+_+") (pintype "passive"))
      (node (ref "C26") (pin "+") (pinfunction "+_+") (pintype "passive"))
      (node (ref "C29") (pin "+") (pinfunction "+_+") (pintype "passive"))
      (node (ref "C30") (pin "+") (pinfunction "+_+") (pintype "passive"))
      (node (ref "J15") (pin "8") (pinfunction "8_8") (pintype "passive"))
      (node (ref "J21") (pin "8") (pinfunction "8_8") (pintype "passive"))
      (node (ref "J25") (pin "1") (pinfunction "1_1") (pintype "passive"))
      (node (ref "J4") (pin "8") (pinfunction "8_8") (pintype "passive"))
      (node (ref "J6") (pin "8") (pinfunction "8_8") (pintype "passive"))
      (node (ref "P1") (pin "3") (pinfunction "VIN_3") (pintype "bidirectional"))
      (node (ref "R5") (pin "2") (pinfunction "2_2") (pintype "passive"))
    )
    (net (code "5") (name "/N$1") (class "Default")
      (node (ref "J1") (pin "1") (pinfunction "1_1") (pintype "passive"))
    )
    (net (code "6") (name "/N$2") (class "Default")
      (node (ref "J2") (pin "1") (pinfunction "1_1") (pintype "passive"))
    )
    (net (code "7") (name "/N$3") (class "Default")
      (node (ref "J1") (pin "3") (pinfunction "3_3") (pintype "passive"))
    )
    (net (code "8") (name "/N$6") (class "Default")
      (node (ref "J2") (pin "3") (pinfunction "3_3") (pintype "passive"))
    )
    (net (code "9") (name "/N$7") (class "Default")
      (node (ref "J1") (pin "7") (pinfunction "7_7") (pintype "passive"))
    )
    (net (code "10") (name "/N$11") (class "Default")
      (node (ref "J2") (pin "7") (pinfunction "7_7") (pintype "passive"))
    )
    (net (code "11") (name "1A_0") (class "Default")
      (node (ref "1A_0") (pin "P$1") (pinfunction "1_P$1") (pintype "bidirectional"))
      (node (ref "J4") (pin "4") (pinfunction "4_4") (pintype "passive"))
      (node (ref "X4") (pin "2") (pinfunction "S_2") (pintype "passive"))
    )
    (net (code "12") (name "1A_1") (class "Default")
      (node (ref "1A_1") (pin "P$1") (pinfunction "1_P$1") (pintype "bidirectional"))
      (node (ref "J6") (pin "4") (pinfunction "4_4") (pintype "passive"))
      (node (ref "X2") (pin "2") (pinfunction "S_2") (pintype "passive"))
    )
    (net (code "13") (name "1A_2") (class "Default")
      (node (ref "1A_2") (pin "P$1") (pinfunction "1_P$1") (pintype "bidirectional"))
      (node (ref "J15") (pin "4") (pinfunction "4_4") (pintype "passive"))
      (node (ref "X3") (pin "2") (pinfunction "S_2") (pintype "passive"))
    )
    (net (code "14") (name "1A_3") (class "Default")
      (node (ref "1A_3") (pin "P$1") (pinfunction "1_P$1") (pintype "bidirectional"))
      (node (ref "J21") (pin "4") (pinfunction "4_4") (pintype "passive"))
      (node (ref "X5") (pin "2") (pinfunction "S_2") (pintype "passive"))
    )
    (net (code "15") (name "1B_0") (class "Default")
      (node (ref "1B_0") (pin "P$1") (pinfunction "1_P$1") (pintype "bidirectional"))
      (node (ref "J4") (pin "3") (pinfunction "3_3") (pintype "passive"))
      (node (ref "X4") (pin "1") (pinfunction "S_1") (pintype "passive"))
    )
    (net (code "16") (name "1B_1") (class "Default")
      (node (ref "1B_1") (pin "P$1") (pinfunction "1_P$1") (pintype "bidirectional"))
      (node (ref "J6") (pin "3") (pinfunction "3_3") (pintype "passive"))
      (node (ref "X2") (pin "1") (pinfunction "S_1") (pintype "passive"))
    )
    (net (code "17") (name "1B_2") (class "Default")
      (node (ref "1B_2") (pin "P$1") (pinfunction "1_P$1") (pintype "bidirectional"))
      (node (ref "J15") (pin "3") (pinfunction "3_3") (pintype "passive"))
      (node (ref "X3") (pin "1") (pinfunction "S_1") (pintype "passive"))
    )
    (net (code "18") (name "1B_3") (class "Default")
      (node (ref "1B_3") (pin "P$1") (pinfunction "1_P$1") (pintype "bidirectional"))
      (node (ref "J21") (pin "3") (pinfunction "3_3") (pintype "passive"))
      (node (ref "X5") (pin "1") (pinfunction "S_1") (pintype "passive"))
    )
    (net (code "19") (name "2A_0") (class "Default")
      (node (ref "2A_0") (pin "P$1") (pinfunction "1_P$1") (pintype "bidirectional"))
      (node (ref "J4") (pin "5") (pinfunction "5_5") (pintype "passive"))
      (node (ref "X4") (pin "3") (pinfunction "S_3") (pintype "passive"))
    )
    (net (code "20") (name "2A_1") (class "Default")
      (node (ref "2A_1") (pin "P$1") (pinfunction "1_P$1") (pintype "bidirectional"))
      (node (ref "J6") (pin "5") (pinfunction "5_5") (pintype "passive"))
      (node (ref "X2") (pin "3") (pinfunction "S_3") (pintype "passive"))
    )
    (net (code "21") (name "2A_2") (class "Default")
      (node (ref "2A_2") (pin "P$1") (pinfunction "1_P$1") (pintype "bidirectional"))
      (node (ref "J15") (pin "5") (pinfunction "5_5") (pintype "passive"))
      (node (ref "X3") (pin "3") (pinfunction "S_3") (pintype "passive"))
    )
    (net (code "22") (name "2A_3") (class "Default")
      (node (ref "2A_3") (pin "P$1") (pinfunction "1_P$1") (pintype "bidirectional"))
      (node (ref "J21") (pin "5") (pinfunction "5_5") (pintype "passive"))
      (node (ref "X5") (pin "3") (pinfunction "S_3") (pintype "passive"))
    )
    (net (code "23") (name "2B_0") (class "Default")
      (node (ref "2B_0") (pin "P$1") (pinfunction "1_P$1") (pintype "bidirectional"))
      (node (ref "J4") (pin "6") (pinfunction "6_6") (pintype "passive"))
      (node (ref "X4") (pin "4") (pinfunction "S_4") (pintype "passive"))
    )
    (net (code "24") (name "2B_1") (class "Default")
      (node (ref "2B_1") (pin "P$1") (pinfunction "1_P$1") (pintype "bidirectional"))
      (node (ref "J6") (pin "6") (pinfunction "6_6") (pintype "passive"))
      (node (ref "X2") (pin "4") (pinfunction "S_4") (pintype "passive"))
    )
    (net (code "25") (name "2B_2") (class "Default")
      (node (ref "2B_2") (pin "P$1") (pinfunction "1_P$1") (pintype "bidirectional"))
      (node (ref "J15") (pin "6") (pinfunction "6_6") (pintype "passive"))
      (node (ref "X3") (pin "4") (pinfunction "S_4") (pintype "passive"))
    )
    (net (code "26") (name "2B_3") (class "Default")
      (node (ref "2B_3") (pin "P$1") (pinfunction "1_P$1") (pintype "bidirectional"))
      (node (ref "J21") (pin "6") (pinfunction "6_6") (pintype "passive"))
      (node (ref "X5") (pin "4") (pinfunction "S_4") (pintype "passive"))
    )
    (net (code "27") (name "ADC_AVDD") (class "Default")
      (node (ref "C13") (pin "1") (pinfunction "1_1") (pintype "passive"))
      (node (ref "R2") (pin "1") (pinfunction "1_1") (pintype "passive"))
      (node (ref "U1") (pin "43") (pinfunction "ADC_AVDD_43") (pintype "power_in"))
    )
    (net (code "28") (name "CAN_N") (class "Default")
      (node (ref "CANBUS") (pin "2") (pinfunction "S_2") (pintype "passive"))
      (node (ref "L2") (pin "3") (pinfunction "3_3") (pintype "passive"))
      (node (ref "SJ1") (pin "1") (pinfunction "1_1") (pintype "passive"))
    )
    (net (code "29") (name "CAN_P") (class "Default")
      (node (ref "CANBUS") (pin "1") (pinfunction "S_1") (pintype "passive"))
      (node (ref "L2") (pin "4") (pinfunction "4_4") (pintype "passive"))
      (node (ref "R16") (pin "1") (pinfunction "1_1") (pintype "passive"))
    )
    (net (code "30") (name "CAN_RX") (class "Default")
      (node (ref "U1") (pin "2") (pinfunction "GPIO0_2") (pintype "bidirectional"))
      (node (ref "U3") (pin "4") (pinfunction "RXD_4") (pintype "output"))
    )
    (net (code "31") (name "CAN_TX") (class "Default")
      (node (ref "U1") (pin "3") (pinfunction "GPIO1_3") (pintype "bidirectional"))
      (node (ref "U3") (pin "1") (pinfunction "TXD_1") (pintype "input"))
    )
    (net (code "32") (name "E0_DIR") (class "Default")
      (node (ref "J3") (pin "1") (pinfunction "1_1") (pintype "passive"))
      (node (ref "U1") (pin "38") (pinfunction "GPIO26/ADC0_38") (pintype "bidirectional"))
    )
    (net (code "33") (name "E0_EN") (class "Default")
      (node (ref "J3") (pin "8") (pinfunction "8_8") (pintype "passive"))
      (node (ref "R10") (pin "1") (pinfunction "1_1") (pintype "passive"))
      (node (ref "U1") (pin "41") (pinfunction "GPIO29/ADC3_41") (pintype "bidirectional"))
    )
    (net (code "34") (name "E0_STEP") (class "Default")
      (node (ref "J3") (pin "2") (pinfunction "2_2") (pintype "passive"))
      (node (ref "U1") (pin "39") (pinfunction "GPIO27/ADC1_39") (pintype "bidirectional"))
    )
    (net (code "35") (name "E0_UART") (class "Default")
      (node (ref "J1") (pin "5") (pinfunction "5_5") (pintype "passive"))
      (node (ref "U1") (pin "40") (pinfunction "GPIO28/ADC2_40") (pintype "bidirectional"))
    )
    (net (code "36") (name "E1_DIR") (class "Default")
      (node (ref "J5") (pin "1") (pinfunction "1_1") (pintype "passive"))
      (node (ref "U1") (pin "34") (pinfunction "GPIO22_34") (pintype "bidirectional"))
    )
    (net (code "37") (name "E1_EN") (class "Default")
      (node (ref "J5") (pin "8") (pinfunction "8_8") (pintype "passive"))
      (node (ref "R11") (pin "1") (pinfunction "1_1") (pintype "passive"))
      (node (ref "U1") (pin "37") (pinfunction "GPIO25_37") (pintype "bidirectional"))
    )
    (net (code "38") (name "E1_STEP") (class "Default")
      (node (ref "J5") (pin "2") (pinfunction "2_2") (pintype "passive"))
      (node (ref "U1") (pin "35") (pinfunction "GPIO23_35") (pintype "bidirectional"))
    )
    (net (code "39") (name "E1_UART") (class "Default")
      (node (ref "J2") (pin "5") (pinfunction "5_5") (pintype "passive"))
      (node (ref "U1") (pin "36") (pinfunction "GPIO24_36") (pintype "bidirectional"))
    )
    (net (code "40") (name "E2_DIR") (class "Default")
      (node (ref "J14") (pin "1") (pinfunction "1_1") (pintype "passive"))
      (node (ref "U1") (pin "29") (pinfunction "GPIO18_29") (pintype "bidirectional"))
    )
    (net (code "41") (name "E2_EN") (class "Default")
      (node (ref "J14") (pin "8") (pinfunction "8_8") (pintype "passive"))
      (node (ref "R12") (pin "1") (pinfunction "1_1") (pintype "passive"))
      (node (ref "U1") (pin "32") (pinfunction "GPIO21_32") (pintype "bidirectional"))
    )
    (net (code "42") (name "E2_STEP") (class "Default")
      (node (ref "J14") (pin "2") (pinfunction "2_2") (pintype "passive"))
      (node (ref "U1") (pin "30") (pinfunction "GPIO19_30") (pintype "bidirectional"))
    )
    (net (code "43") (name "E2_UART") (class "Default")
      (node (ref "J13") (pin "5") (pinfunction "5_5") (pintype "passive"))
      (node (ref "U1") (pin "31") (pinfunction "GPIO20_31") (pintype "bidirectional"))
    )
    (net (code "44") (name "E3_DIR") (class "Default")
      (node (ref "J20") (pin "1") (pinfunction "1_1") (pintype "passive"))
      (node (ref "U1") (pin "8") (pinfunction "GPIO6_8") (pintype "bidirectional"))
    )
    (net (code "45") (name "E3_EN") (class "Default")
      (node (ref "J20") (pin "8") (pinfunction "8_8") (pintype "passive"))
      (node (ref "R13") (pin "1") (pinfunction "1_1") (pintype "passive"))
      (node (ref "U1") (pin "5") (pinfunction "GPIO3_5") (pintype "bidirectional"))
    )
    (net (code "46") (name "E3_STEP") (class "Default")
      (node (ref "J20") (pin "2") (pinfunction "2_2") (pintype "passive"))
      (node (ref "U1") (pin "7") (pinfunction "GPIO5_7") (pintype "bidirectional"))
    )
    (net (code "47") (name "E3_UART") (class "Default")
      (node (ref "J19") (pin "5") (pinfunction "5_5") (pintype "passive"))
      (node (ref "U1") (pin "6") (pinfunction "GPIO4_6") (pintype "bidirectional"))
    )
    (net (code "48") (name "FS0") (class "Default")
      (node (ref "FS0") (pin "P$1") (pinfunction "1_P$1") (pintype "bidirectional"))
      (node (ref "U1") (pin "4") (pinfunction "GPIO2_4") (pintype "bidirectional"))
      (node (ref "X6") (pin "3") (pinfunction "S_3") (pintype "passive"))
    )
    (net (code "49") (name "FS1") (class "Default")
      (node (ref "FS1") (pin "P$1") (pinfunction "1_P$1") (pintype "bidirectional"))
      (node (ref "U1") (pin "9") (pinfunction "GPIO7_9") (pintype "bidirectional"))
      (node (ref "X8") (pin "3") (pinfunction "S_3") (pintype "passive"))
    )
    (net (code "50") (name "FS2") (class "Default")
      (node (ref "FS2") (pin "P$1") (pinfunction "1_P$1") (pintype "bidirectional"))
      (node (ref "U1") (pin "27") (pinfunction "GPIO16_27") (pintype "bidirectional"))
      (node (ref "X7") (pin "3") (pinfunction "S_3") (pintype "passive"))
    )
    (net (code "51") (name "FS3") (class "Default")
      (node (ref "FS3") (pin "P$1") (pinfunction "1_P$1") (pintype "bidirectional"))
      (node (ref "U1") (pin "28") (pinfunction "GPIO17_28") (pintype "bidirectional"))
      (node (ref "X9") (pin "3") (pinfunction "S_3") (pintype "passive"))
    )
    (net (code "52") (name "GND") (class "Default")
      (node (ref "BOOT") (pin "1") (pinfunction "1_1") (pintype "bidirectional"))
      (node (ref "C1") (pin "2") (pinfunction "2_2") (pintype "passive"))
      (node (ref "C10") (pin "2") (pinfunction "2_2") (pintype "passive"))
      (node (ref "C11") (pin "2") (pinfunction "2_2") (pintype "passive"))
      (node (ref "C12") (pin "2") (pinfunction "2_2") (pintype "passive"))
      (node (ref "C13") (pin "2") (pinfunction "2_2") (pintype "passive"))
      (node (ref "C14") (pin "2") (pinfunction "2_2") (pintype "passive"))
      (node (ref "C15") (pin "2") (pinfunction "2_2") (pintype "passive"))
      (node (ref "C16") (pin "2") (pinfunction "2_2") (pintype "passive"))
      (node (ref "C17") (pin "2") (pinfunction "2_2") (pintype "passive"))
      (node (ref "C18") (pin "2") (pinfunction "2_2") (pintype "passive"))
      (node (ref "C19") (pin "2") (pinfunction "2_2") (pintype "passive"))
      (node (ref "C2") (pin "1") (pinfunction "1_1") (pintype "passive"))
      (node (ref "C21") (pin "2") (pinfunction "2_2") (pintype "passive"))
      (node (ref "C22") (pin "2") (pinfunction "2_2") (pintype "passive"))
      (node (ref "C24") (pin "2") (pinfunction "2_2") (pintype "passive"))
      (node (ref "C25") (pin "-") (pinfunction "-_-") (pintype "passive"))
      (node (ref "C26") (pin "-") (pinfunction "-_-") (pintype "passive"))
      (node (ref "C27") (pin "2") (pinfunction "2_2") (pintype "passive"))
      (node (ref "C28") (pin "2") (pinfunction "2_2") (pintype "passive"))
      (node (ref "C29") (pin "-") (pinfunction "-_-") (pintype "passive"))
      (node (ref "C3") (pin "2") (pinfunction "2_2") (pintype "passive"))
      (node (ref "C30") (pin "-") (pinfunction "-_-") (pintype "passive"))
      (node (ref "C39") (pin "1") (pinfunction "1_1") (pintype "passive"))
      (node (ref "C4") (pin "2") (pinfunction "2_2") (pintype "passive"))
      (node (ref "C5") (pin "2") (pinfunction "2_2") (pintype "passive"))
      (node (ref "C6") (pin "2") (pinfunction "2_2") (pintype "passive"))
      (node (ref "C7") (pin "2") (pinfunction "2_2") (pintype "passive"))
      (node (ref "C8") (pin "2") (pinfunction "2_2") (pintype "passive"))
      (node (ref "C9") (pin "2") (pinfunction "2_2") (pintype "passive"))
      (node (ref "D2") (pin "2") (pinfunction "GND_2") (pintype "power_in"))
      (node (ref "D3") (pin "C") (pinfunction "C_C") (pintype "passive"))
      (node (ref "GND") (pin "P$1") (pinfunction "1_P$1") (pintype "bidirectional"))
      (node (ref "J15") (pin "1") (pinfunction "1_1") (pintype "passive"))
      (node (ref "J15") (pin "7") (pinfunction "7_7") (pintype "passive"))
      (node (ref "J21") (pin "1") (pinfunction "1_1") (pintype "passive"))
      (node (ref "J21") (pin "7") (pinfunction "7_7") (pintype "passive"))
      (node (ref "J25") (pin "2") (pinfunction "2_2") (pintype "passive"))
      (node (ref "J4") (pin "1") (pinfunction "1_1") (pintype "passive"))
      (node (ref "J4") (pin "7") (pinfunction "7_7") (pintype "passive"))
      (node (ref "J6") (pin "1") (pinfunction "1_1") (pintype "passive"))
      (node (ref "J6") (pin "7") (pinfunction "7_7") (pintype "passive"))
      (node (ref "P1") (pin "1") (pinfunction "GND_1") (pintype "bidirectional"))
      (node (ref "P2") (pin "2") (pinfunction "GND_2") (pintype "input"))
      (node (ref "R14") (pin "2") (pinfunction "2_2") (pintype "passive"))
      (node (ref "R17") (pin "2") (pinfunction "2_2") (pintype "passive"))
      (node (ref "R18") (pin "1") (pinfunction "1_1") (pintype "passive"))
      (node (ref "R19") (pin "2") (pinfunction "2_2") (pintype "passive"))
      (node (ref "R20") (pin "1") (pinfunction "1_1") (pintype "passive"))
      (node (ref "R21") (pin "2") (pinfunction "2_2") (pintype "passive"))
      (node (ref "R22") (pin "1") (pinfunction "1_1") (pintype "passive"))
      (node (ref "R31") (pin "1") (pinfunction "1_1") (pintype "passive"))
      (node (ref "R6") (pin "1") (pinfunction "1_1") (pintype "passive"))
      (node (ref "R9") (pin "1") (pinfunction "1_1") (pintype "passive"))
      (node (ref "RESET") (pin "1") (pinfunction "1_1") (pintype "bidirectional"))
      (node (ref "U1") (pin "19") (pinfunction "TESTEN_19") (pintype "passive"))
      (node (ref "U1") (pin "57") (pinfunction "GND_57") (pintype "passive"))
      (node (ref "U2") (pin "4") (pinfunction "GND_4") (pintype "passive"))
      (node (ref "U3") (pin "2") (pinfunction "GND_2") (pintype "power_in"))
      (node (ref "U3") (pin "8") (pinfunction "STBY_8") (pintype "input"))
      (node (ref "USB") (pin "1") (pinfunction "GND_1") (pintype "power_in"))
      (node (ref "USB") (pin "12") (pinfunction "GND2_12") (pintype "power_in"))
      (node (ref "USB") (pin "13") (pinfunction "SHLD_13") (pintype "passive"))
      (node (ref "USB") (pin "14") (pinfunction "SHLD_14") (pintype "passive"))
      (node (ref "USB") (pin "15") (pinfunction "SHLD_15") (pintype "passive"))
      (node (ref "USB") (pin "16") (pinfunction "SHLD_16") (pintype "passive"))
      (node (ref "USB") (pin "18") (pinfunction "SHLD_18") (pintype "passive"))
      (node (ref "USB") (pin "19") (pinfunction "SHLD_19") (pintype "passive"))
      (node (ref "USB") (pin "20") (pinfunction "SHLD_20") (pintype "passive"))
      (node (ref "USB") (pin "21") (pinfunction "SHLD_21") (pintype "passive"))
      (node (ref "USB") (pin "24") (pinfunction "SHLD_24") (pintype "passive"))
      (node (ref "USB") (pin "25") (pinfunction "SHLD_25") (pintype "passive"))
      (node (ref "USB") (pin "26") (pinfunction "SHLD_26") (pintype "passive"))
      (node (ref "USB") (pin "27") (pinfunction "SHLD_27") (pintype "passive"))
      (node (ref "USB") (pin "28") (pinfunction "SHLD_28") (pintype "passive"))
      (node (ref "USB") (pin "29") (pinfunction "SHLD_29") (pintype "passive"))
      (node (ref "USB") (pin "37") (pinfunction "SHLD_37") (pintype "passive"))
      (node (ref "USB") (pin "39") (pinfunction "SHLD_39") (pintype "passive"))
      (node (ref "USB") (pin "41") (pinfunction "SHLD_41") (pintype "passive"))
      (node (ref "USB") (pin "43") (pinfunction "SHLD_43") (pintype "passive"))
      (node (ref "X1") (pin "P$2") (pinfunction "GND_P$2") (pintype "bidirectional"))
      (node (ref "X1") (pin "P$4") (pinfunction "GND_P$4") (pintype "bidirectional"))
      (node (ref "X6") (pin "1") (pinfunction "S_1") (pintype "passive"))
      (node (ref "X7") (pin "1") (pinfunction "S_1") (pintype "passive"))
      (node (ref "X8") (pin "1") (pinfunction "S_1") (pintype "passive"))
      (node (ref "X9") (pin "1") (pinfunction "S_1") (pintype "passive"))
    )
    (net (code "53") (name "LOAD_0") (class "Default")
      (node (ref "LOAD0") (pin "1") (pinfunction "1_1") (pintype "bidirectional"))
      (node (ref "LOAD_0") (pin "P$1") (pinfunction "1_P$1") (pintype "bidirectional"))
      (node (ref "R14") (pin "1") (pinfunction "1_1") (pintype "passive"))
      (node (ref "U1") (pin "11") (pinfunction "GPIO8_11") (pintype "bidirectional"))
      (node (ref "X18") (pin "1") (pinfunction "S_1") (pintype "passive"))
    )
    (net (code "54") (name "LOAD_1") (class "Default")
      (node (ref "LOAD1") (pin "1") (pinfunction "1_1") (pintype "bidirectional"))
      (node (ref "LOAD_1") (pin "P$1") (pinfunction "1_P$1") (pintype "bidirectional"))
      (node (ref "R17") (pin "1") (pinfunction "1_1") (pintype "passive"))
      (node (ref "U1") (pin "13") (pinfunction "GPIO10_13") (pintype "bidirectional"))
      (node (ref "X22") (pin "1") (pinfunction "S_1") (pintype "passive"))
    )
    (net (code "55") (name "LOAD_2") (class "Default")
      (node (ref "LOAD2") (pin "1") (pinfunction "1_1") (pintype "bidirectional"))
      (node (ref "LOAD_2") (pin "P$1") (pinfunction "1_P$1") (pintype "bidirectional"))
      (node (ref "R19") (pin "1") (pinfunction "1_1") (pintype "passive"))
      (node (ref "U1") (pin "15") (pinfunction "GPIO12_15") (pintype "bidirectional"))
      (node (ref "X20") (pin "1") (pinfunction "S_1") (pintype "passive"))
    )
    (net (code "56") (name "LOAD_3") (class "Default")
      (node (ref "LOAD3") (pin "1") (pinfunction "1_1") (pintype "bidirectional"))
      (node (ref "LOAD_3") (pin "P$1") (pinfunction "1_P$1") (pintype "bidirectional"))
      (node (ref "R21") (pin "1") (pinfunction "1_1") (pintype "passive"))
      (node (ref "U1") (pin "17") (pinfunction "GPIO14_17") (pintype "bidirectional"))
      (node (ref "X24") (pin "1") (pinfunction "S_1") (pintype "passive"))
    )
    (net (code "57") (name "MS1_0") (class "Default")
      (node (ref "J1") (pin "2") (pinfunction "2_2") (pintype "passive"))
      (node (ref "J3") (pin "7") (pinfunction "7_7") (pintype "passive"))
    )
    (net (code "58") (name "MS1_1") (class "Default")
      (node (ref "J2") (pin "2") (pinfunction "2_2") (pintype "passive"))
      (node (ref "J5") (pin "7") (pinfunction "7_7") (pintype "passive"))
    )
    (net (code "59") (name "MS1_2") (class "Default")
      (node (ref "J13") (pin "2") (pinfunction "2_2") (pintype "passive"))
      (node (ref "J14") (pin "7") (pinfunction "7_7") (pintype "passive"))
    )
    (net (code "60") (name "MS1_3") (class "Default")
      (node (ref "J19") (pin "2") (pinfunction "2_2") (pintype "passive"))
      (node (ref "J20") (pin "7") (pinfunction "7_7") (pintype "passive"))
    )
    (net (code "61") (name "MS2_0") (class "Default")
      (node (ref "J1") (pin "4") (pinfunction "4_4") (pintype "passive"))
      (node (ref "J3") (pin "6") (pinfunction "6_6") (pintype "passive"))
    )
    (net (code "62") (name "MS2_1") (class "Default")
      (node (ref "J2") (pin "4") (pinfunction "4_4") (pintype "passive"))
      (node (ref "J5") (pin "6") (pinfunction "6_6") (pintype "passive"))
    )
    (net (code "63") (name "MS2_2") (class "Default")
      (node (ref "J13") (pin "4") (pinfunction "4_4") (pintype "passive"))
      (node (ref "J14") (pin "6") (pinfunction "6_6") (pintype "passive"))
    )
    (net (code "64") (name "MS2_3") (class "Default")
      (node (ref "J19") (pin "4") (pinfunction "4_4") (pintype "passive"))
      (node (ref "J20") (pin "6") (pinfunction "6_6") (pintype "passive"))
    )
    (net (code "65") (name "MS3_0") (class "Default")
      (node (ref "J1") (pin "6") (pinfunction "6_6") (pintype "passive"))
      (node (ref "J3") (pin "5") (pinfunction "5_5") (pintype "passive"))
    )
    (net (code "66") (name "MS3_1") (class "Default")
      (node (ref "J2") (pin "6") (pinfunction "6_6") (pintype "passive"))
      (node (ref "J5") (pin "5") (pinfunction "5_5") (pintype "passive"))
    )
    (net (code "67") (name "MS3_2") (class "Default")
      (node (ref "J13") (pin "6") (pinfunction "6_6") (pintype "passive"))
      (node (ref "J14") (pin "5") (pinfunction "5_5") (pintype "passive"))
    )
    (net (code "68") (name "MS3_3") (class "Default")
      (node (ref "J19") (pin "6") (pinfunction "6_6") (pintype "passive"))
      (node (ref "J20") (pin "5") (pinfunction "5_5") (pintype "passive"))
    )
    (net (code "69") (name "Net-(BOOT-Pad2)") (class "Default")
      (node (ref "BOOT") (pin "2") (pinfunction "2_2") (pintype "bidirectional"))
      (node (ref "R23") (pin "2") (pinfunction "2_2") (pintype "passive"))
    )
    (net (code "70") (name "Net-(C23-Pad1)") (class "Default")
      (node (ref "C23") (pin "1") (pinfunction "1_1") (pintype "passive"))
      (node (ref "R7") (pin "1") (pinfunction "1_1") (pintype "passive"))
      (node (ref "R8") (pin "2") (pinfunction "2_2") (pintype "passive"))
    )
    (net (code "71") (name "Net-(D1-A)") (class "Default")
      (node (ref "D1") (pin "2") (pinfunction "A_2") (pintype "passive"))
      (node (ref "F1") (pin "1") (pinfunction "1_1") (pintype "passive"))
    )
    (net (code "72") (name "Net-(D2-I{slash}O1)") (class "Default")
      (node (ref "D2") (pin "1") (pinfunction "I/O1_2_1") (pintype "bidirectional"))
      (node (ref "D2") (pin "6") (pinfunction "I/O1_6") (pintype "bidirectional"))
      (node (ref "IO1") (pin "P$1") (pinfunction "1_P$1") (pintype "bidirectional"))
      (node (ref "R29") (pin "1") (pinfunction "1_1") (pintype "passive"))
      (node (ref "USB") (pin "6") (pinfunction "AD+_6") (pintype "passive"))
      (node (ref "USB") (pin "8") (pinfunction "BD+_8") (pintype "passive"))
    )
    (net (code "73") (name "Net-(D2-I{slash}O2)") (class "Default")
      (node (ref "D2") (pin "3") (pinfunction "I/O2_2_3") (pintype "bidirectional"))
      (node (ref "D2") (pin "4") (pinfunction "I/O2_4") (pintype "bidirectional"))
      (node (ref "IO2") (pin "P$1") (pinfunction "1_P$1") (pintype "bidirectional"))
      (node (ref "R30") (pin "1") (pinfunction "1_1") (pintype "passive"))
      (node (ref "USB") (pin "5") (pinfunction "BD-_5") (pintype "passive"))
      (node (ref "USB") (pin "7") (pinfunction "AD-_7") (pintype "passive"))
    )
    (net (code "74") (name "Net-(D2-VBUS)") (class "Default")
      (node (ref "D2") (pin "5") (pinfunction "VBUS_5") (pintype "power_in"))
      (node (ref "F1") (pin "2") (pinfunction "2_2") (pintype "passive"))
      (node (ref "SJ3") (pin "1") (pinfunction "1_1") (pintype "passive"))
    )
    (net (code "75") (name "Net-(D3-PadA)") (class "Default")
      (node (ref "D3") (pin "A") (pinfunction "A_A") (pintype "passive"))
      (node (ref "R15") (pin "1") (pinfunction "1_1") (pintype "passive"))
    )
    (net (code "76") (name "Net-(P1-BOOT)") (class "Default")
      (node (ref "C20") (pin "1") (pinfunction "1_1") (pintype "passive"))
      (node (ref "P1") (pin "6") (pinfunction "BOOT_6") (pintype "bidirectional"))
    )
    (net (code "77") (name "Net-(P1-EN)") (class "Default")
      (node (ref "P1") (pin "5") (pinfunction "EN_5") (pintype "bidirectional"))
      (node (ref "R5") (pin "1") (pinfunction "1_1") (pintype "passive"))
      (node (ref "R6") (pin "2") (pinfunction "2_2") (pintype "passive"))
    )
    (net (code "78") (name "Net-(P1-FB)") (class "Default")
      (node (ref "C23") (pin "2") (pinfunction "2_2") (pintype "passive"))
      (node (ref "P1") (pin "4") (pinfunction "FB_4") (pintype "bidirectional"))
      (node (ref "R8") (pin "1") (pinfunction "1_1") (pintype "passive"))
      (node (ref "R9") (pin "2") (pinfunction "2_2") (pintype "passive"))
    )
    (net (code "79") (name "Net-(P1-SW)") (class "Default")
      (node (ref "C20") (pin "2") (pinfunction "2_2") (pintype "passive"))
      (node (ref "L1") (pin "1") (pinfunction "1_1") (pintype "bidirectional"))
      (node (ref "P1") (pin "2") (pinfunction "SW_2") (pintype "bidirectional"))
    )
    (net (code "80") (name "Net-(R1-Pad1)") (class "Default")
      (node (ref "R1") (pin "1") (pinfunction "1_1") (pintype "passive"))
      (node (ref "R2") (pin "2") (pinfunction "2_2") (pintype "passive"))
    )
    (net (code "81") (name "Net-(R16-Pad2)") (class "Default")
      (node (ref "R16") (pin "2") (pinfunction "2_2") (pintype "passive"))
      (node (ref "SJ1") (pin "2") (pinfunction "2_2") (pintype "passive"))
    )
    (net (code "82") (name "Net-(U3-CANH)") (class "Default")
      (node (ref "L2") (pin "1") (pinfunction "1_1") (pintype "passive"))
      (node (ref "U3") (pin "7") (pinfunction "CANH_7") (pintype "output"))
    )
    (net (code "83") (name "Net-(U3-CANL)") (class "Default")
      (node (ref "L2") (pin "2") (pinfunction "2_2") (pintype "passive"))
      (node (ref "U3") (pin "6") (pinfunction "CANL_6") (pintype "output"))
    )
    (net (code "84") (name "Net-(X1-P2)") (class "Default")
      (node (ref "C2") (pin "2") (pinfunction "2_2") (pintype "passive"))
      (node (ref "R3") (pin "1") (pinfunction "1_1") (pintype "passive"))
      (node (ref "X1") (pin "P$3") (pinfunction "P2_P$3") (pintype "bidirectional"))
    )
    (net (code "85") (name "OSC_IN") (class "Default")
      (node (ref "C1") (pin "1") (pinfunction "1_1") (pintype "passive"))
      (node (ref "R4") (pin "2") (pinfunction "2_2") (pintype "passive"))
      (node (ref "U1") (pin "20") (pinfunction "XIN_20") (pintype "passive"))
      (node (ref "X1") (pin "P$1") (pinfunction "P1_P$1") (pintype "bidirectional"))
    )
    (net (code "86") (name "OSC_OUT") (class "Default")
      (node (ref "R3") (pin "2") (pinfunction "2_2") (pintype "passive"))
      (node (ref "R4") (pin "1") (pinfunction "1_1") (pintype "passive"))
      (node (ref "U1") (pin "21") (pinfunction "XOUT_21") (pintype "output"))
    )
    (net (code "87") (name "QSPI_SCK") (class "Default")
      (node (ref "U1") (pin "52") (pinfunction "QSPI_SCLK_52") (pintype "passive"))
      (node (ref "U2") (pin "6") (pinfunction "CLK_6") (pintype "passive"))
    )
    (net (code "88") (name "QSPI_SD0") (class "Default")
      (node (ref "U1") (pin "53") (pinfunction "QSPI_SD0_53") (pintype "bidirectional"))
      (node (ref "U2") (pin "5") (pinfunction "DI_(IO0)_5") (pintype "passive"))
    )
    (net (code "89") (name "QSPI_SD1") (class "Default")
      (node (ref "U1") (pin "55") (pinfunction "QSPI_SD1_55") (pintype "bidirectional"))
      (node (ref "U2") (pin "2") (pinfunction "DO_(IO1)_2") (pintype "passive"))
    )
    (net (code "90") (name "QSPI_SD2") (class "Default")
      (node (ref "U1") (pin "54") (pinfunction "QSPI_SD2_54") (pintype "bidirectional"))
      (node (ref "U2") (pin "3") (pinfunction "/WP_(IO2)_3") (pintype "passive"))
    )
    (net (code "91") (name "QSPI_SD3") (class "Default")
      (node (ref "U1") (pin "51") (pinfunction "QSPI_SD3_51") (pintype "bidirectional"))
      (node (ref "U2") (pin "7") (pinfunction "/RESET_(IO3)_7") (pintype "passive"))
    )
    (net (code "92") (name "QSPI_SS") (class "Default")
      (node (ref "R23") (pin "1") (pinfunction "1_1") (pintype "passive"))
      (node (ref "R24") (pin "1") (pinfunction "1_1") (pintype "passive"))
      (node (ref "U1") (pin "56") (pinfunction "QSPI_SS_N_56") (pintype "passive"))
      (node (ref "U2") (pin "1") (pinfunction "/CS_1") (pintype "passive"))
    )
    (net (code "93") (name "RESET") (class "Default")
      (node (ref "C39") (pin "2") (pinfunction "2_2") (pintype "passive"))
      (node (ref "R25") (pin "1") (pinfunction "1_1") (pintype "passive"))
      (node (ref "RESET") (pin "2") (pinfunction "2_2") (pintype "bidirectional"))
      (node (ref "U1") (pin "26") (pinfunction "RUN_26") (pintype "passive"))
    )
    (net (code "94") (name "RST_0") (class "Default")
      (node (ref "J1") (pin "8") (pinfunction "8_8") (pintype "passive"))
      (node (ref "J3") (pin "3") (pinfunction "3_3") (pintype "passive"))
      (node (ref "J3") (pin "4") (pinfunction "4_4") (pintype "passive"))
    )
    (net (code "95") (name "RST_1") (class "Default")
      (node (ref "J2") (pin "8") (pinfunction "8_8") (pintype "passive"))
      (node (ref "J5") (pin "3") (pinfunction "3_3") (pintype "passive"))
      (node (ref "J5") (pin "4") (pinfunction "4_4") (pintype "passive"))
    )
    (net (code "96") (name "RST_2") (class "Default")
      (node (ref "J13") (pin "8") (pinfunction "8_8") (pintype "passive"))
      (node (ref "J14") (pin "3") (pinfunction "3_3") (pintype "passive"))
      (node (ref "J14") (pin "4") (pinfunction "4_4") (pintype "passive"))
    )
    (net (code "97") (name "RST_3") (class "Default")
      (node (ref "J19") (pin "8") (pinfunction "8_8") (pintype "passive"))
      (node (ref "J20") (pin "3") (pinfunction "3_3") (pintype "passive"))
      (node (ref "J20") (pin "4") (pinfunction "4_4") (pintype "passive"))
    )
    (net (code "98") (name "SWCLK") (class "Default")
      (node (ref "U1") (pin "24") (pinfunction "SWCLK_24") (pintype "passive"))
    )
    (net (code "99") (name "SWDIO") (class "Default")
      (node (ref "U1") (pin "25") (pinfunction "SWDIO_25") (pintype "passive"))
    )
    (net (code "100") (name "UNLOAD_0") (class "Default")
      (node (ref "R31") (pin "2") (pinfunction "2_2") (pintype "passive"))
      (node (ref "U1") (pin "12") (pinfunction "GPIO9_12") (pintype "bidirectional"))
      (node (ref "UNLOAD0") (pin "1") (pinfunction "1_1") (pintype "bidirectional"))
      (node (ref "UNLOAD_0") (pin "P$1") (pinfunction "1_P$1") (pintype "bidirectional"))
      (node (ref "X19") (pin "1") (pinfunction "S_1") (pintype "passive"))
    )
    (net (code "101") (name "UNLOAD_1") (class "Default")
      (node (ref "R18") (pin "2") (pinfunction "2_2") (pintype "passive"))
      (node (ref "U1") (pin "14") (pinfunction "GPIO11_14") (pintype "bidirectional"))
      (node (ref "UNLOAD1") (pin "1") (pinfunction "1_1") (pintype "bidirectional"))
      (node (ref "UNLOAD_1") (pin "P$1") (pinfunction "1_P$1") (pintype "bidirectional"))
      (node (ref "X23") (pin "1") (pinfunction "S_1") (pintype "passive"))
    )
    (net (code "102") (name "UNLOAD_2") (class "Default")
      (node (ref "R20") (pin "2") (pinfunction "2_2") (pintype "passive"))
      (node (ref "U1") (pin "16") (pinfunction "GPIO13_16") (pintype "bidirectional"))
      (node (ref "UNLOAD2") (pin "1") (pinfunction "1_1") (pintype "bidirectional"))
      (node (ref "UNLOAD_2") (pin "P$1") (pinfunction "1_P$1") (pintype "bidirectional"))
      (node (ref "X21") (pin "1") (pinfunction "S_1") (pintype "passive"))
    )
    (net (code "103") (name "UNLOAD_3") (class "Default")
      (node (ref "R22") (pin "2") (pinfunction "2_2") (pintype "passive"))
      (node (ref "U1") (pin "18") (pinfunction "GPIO15_18") (pintype "bidirectional"))
      (node (ref "UNLOAD3") (pin "1") (pinfunction "1_1") (pintype "bidirectional"))
      (node (ref "UNLOAD_3") (pin "P$1") (pinfunction "1_P$1") (pintype "bidirectional"))
      (node (ref "X25") (pin "1") (pinfunction "S_1") (pintype "passive"))
    )
    (net (code "104") (name "USB_N") (class "Default")
      (node (ref "R30") (pin "2") (pinfunction "2_2") (pintype "passive"))
      (node (ref "U1") (pin "46") (pinfunction "USB_DM_46") (pintype "passive"))
    )
    (net (code "105") (name "USB_P") (class "Default")
      (node (ref "R29") (pin "2") (pinfunction "2_2") (pintype "passive"))
      (node (ref "U1") (pin "47") (pinfunction "USB_DP_47") (pintype "passive"))
    )
    (net (code "106") (name "VBUS") (class "Default")
      (node (ref "SJ3") (pin "2") (pinfunction "2_2") (pintype "passive"))
      (node (ref "USB") (pin "11") (pinfunction "VBUS2_11") (pintype "power_in"))
      (node (ref "USB") (pin "2") (pinfunction "VBUS_2") (pintype "power_in"))
    )
    (net (code "107") (name "unconnected-(J13-Pad1)") (class "Default")
      (node (ref "J13") (pin "1") (pinfunction "1_1") (pintype "passive"))
    )
    (net (code "108") (name "unconnected-(J13-Pad3)") (class "Default")
      (node (ref "J13") (pin "3") (pinfunction "3_3") (pintype "passive"))
    )
    (net (code "109") (name "unconnected-(J13-Pad7)") (class "Default")
      (node (ref "J13") (pin "7") (pinfunction "7_7") (pintype "passive"))
    )
    (net (code "110") (name "unconnected-(J19-Pad1)") (class "Default")
      (node (ref "J19") (pin "1") (pinfunction "1_1") (pintype "passive"))
    )
    (net (code "111") (name "unconnected-(J19-Pad3)") (class "Default")
      (node (ref "J19") (pin "3") (pinfunction "3_3") (pintype "passive"))
    )
    (net (code "112") (name "unconnected-(J19-Pad7)") (class "Default")
      (node (ref "J19") (pin "7") (pinfunction "7_7") (pintype "passive"))
    )
    (net (code "113") (name "unconnected-(P2-NC-Pad4)") (class "Default")
      (node (ref "P2") (pin "4") (pinfunction "NC_4") (pintype "no_connect"))
    )
    (net (code "114") (name "unconnected-(USB-CC1-Pad3)") (class "Default")
      (node (ref "USB") (pin "3") (pinfunction "CC1_3") (pintype "passive"))
    )
    (net (code "115") (name "unconnected-(USB-CC2-Pad9)") (class "Default")
      (node (ref "USB") (pin "9") (pinfunction "CC2_9") (pintype "passive"))
    )
    (net (code "116") (name "unconnected-(USB-SBU1-Pad10)") (class "Default")
      (node (ref "USB") (pin "10") (pinfunction "SBU1_10") (pintype "passive"))
    )
    (net (code "117") (name "unconnected-(USB-SBU2-Pad4)") (class "Default")
      (node (ref "USB") (pin "4") (pinfunction "SBU2_4") (pintype "passive"))
    )
  )
)
